# oresat0-1u-backplane.net
KiCad netlist of a schematic drawn in EAGLE
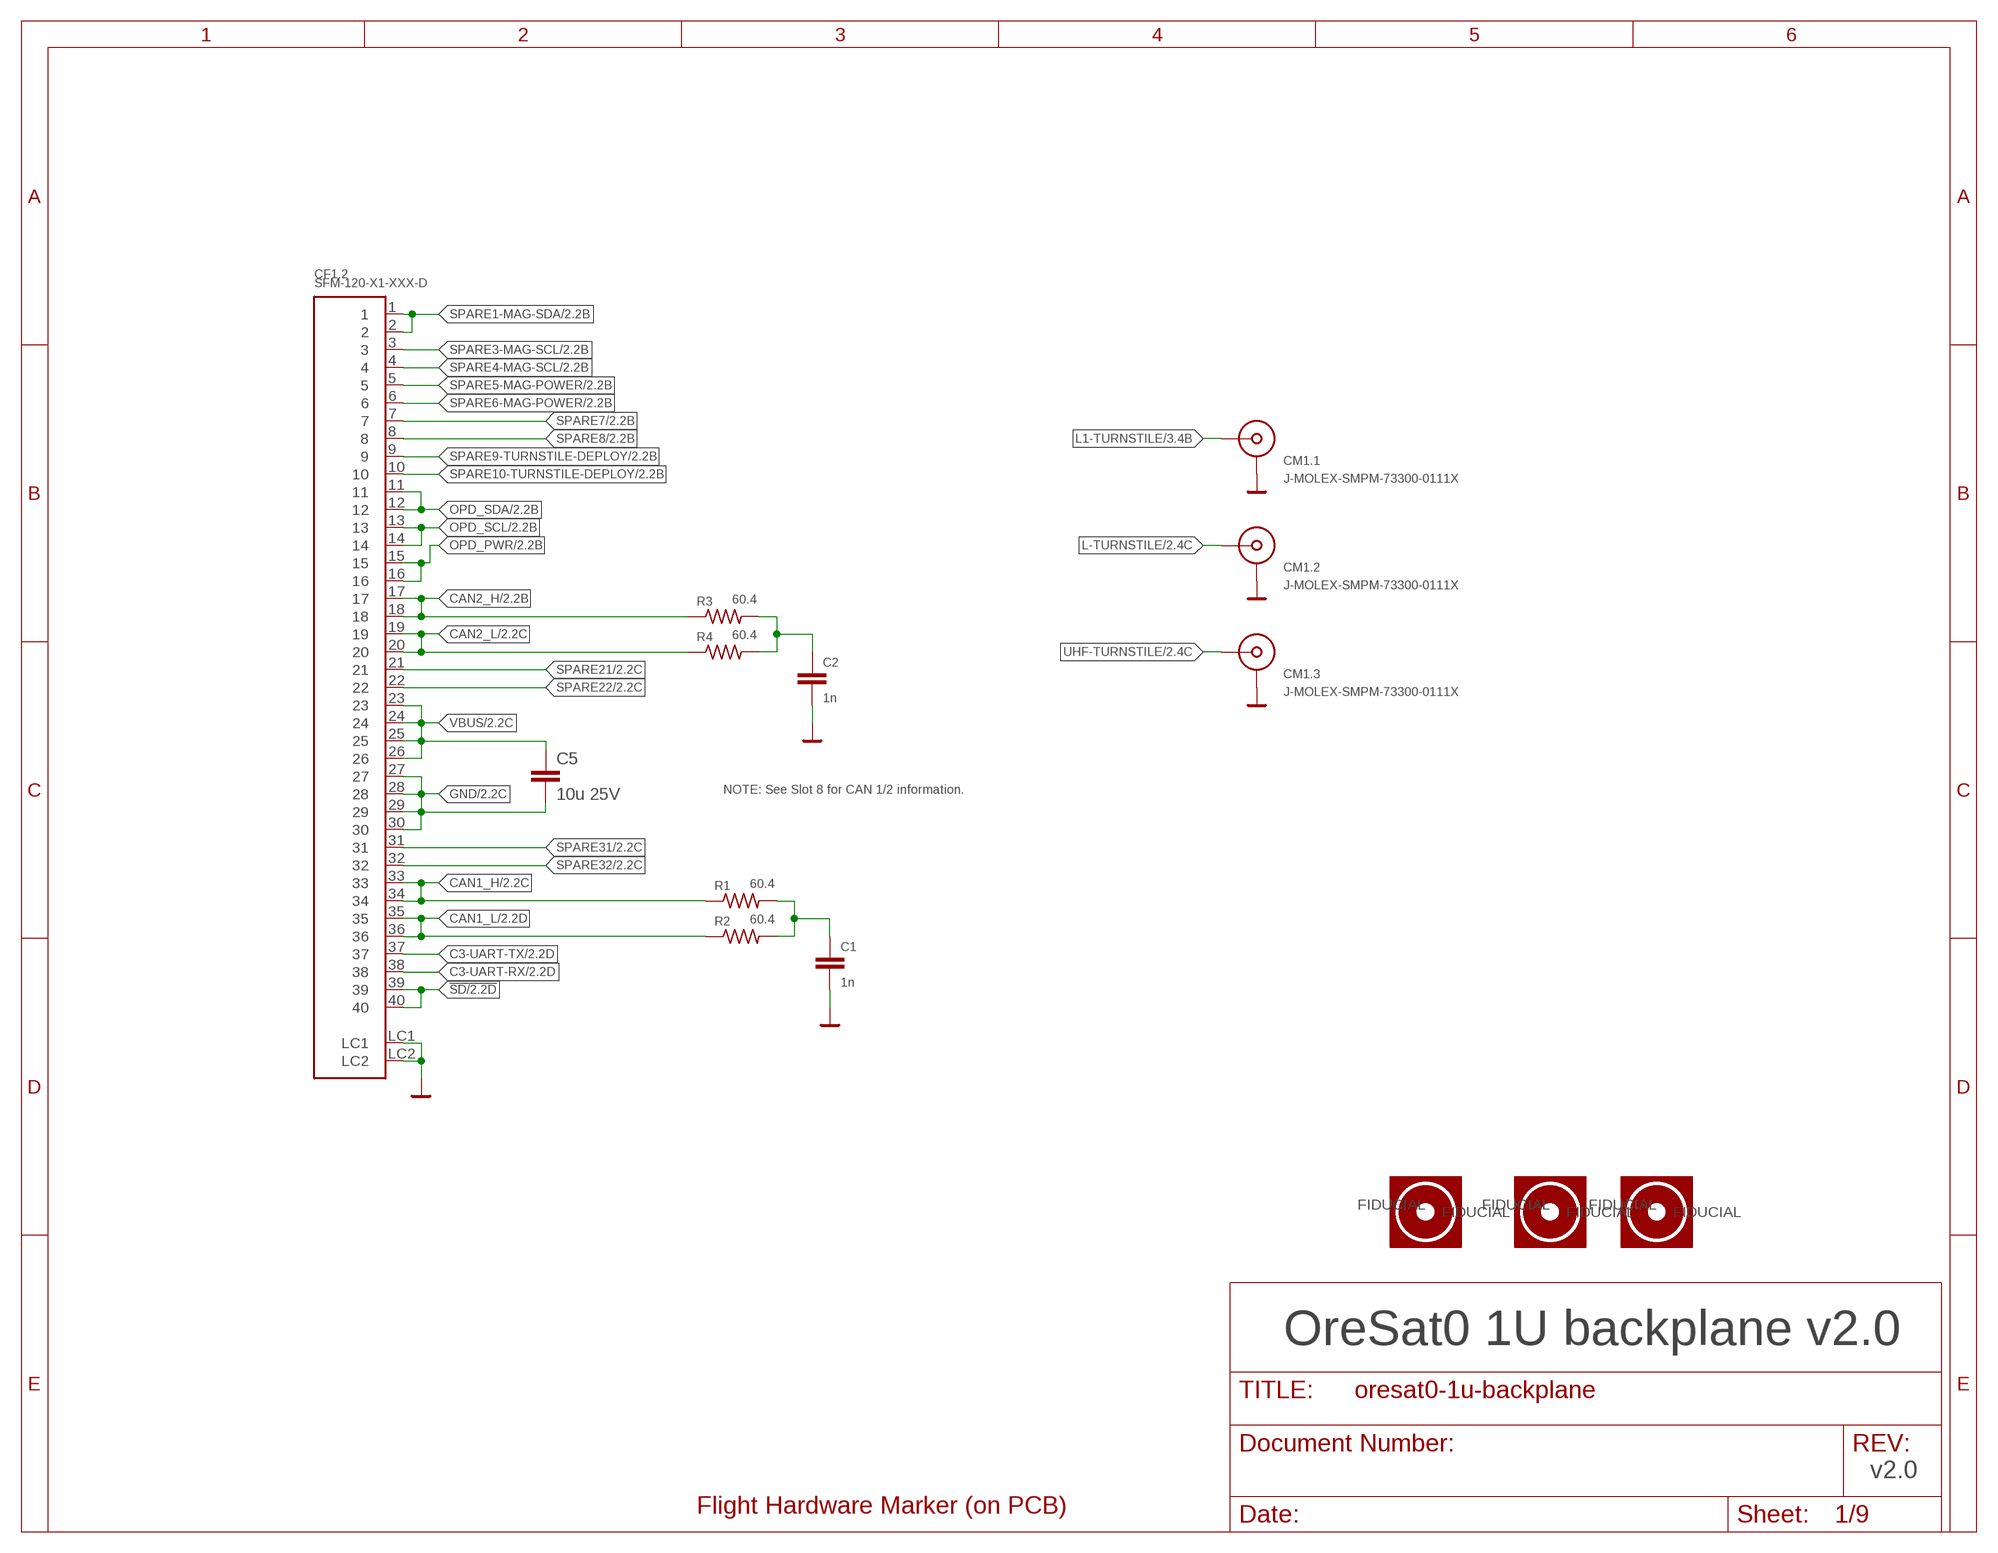
[diagram p0: schematic, sheet 1]
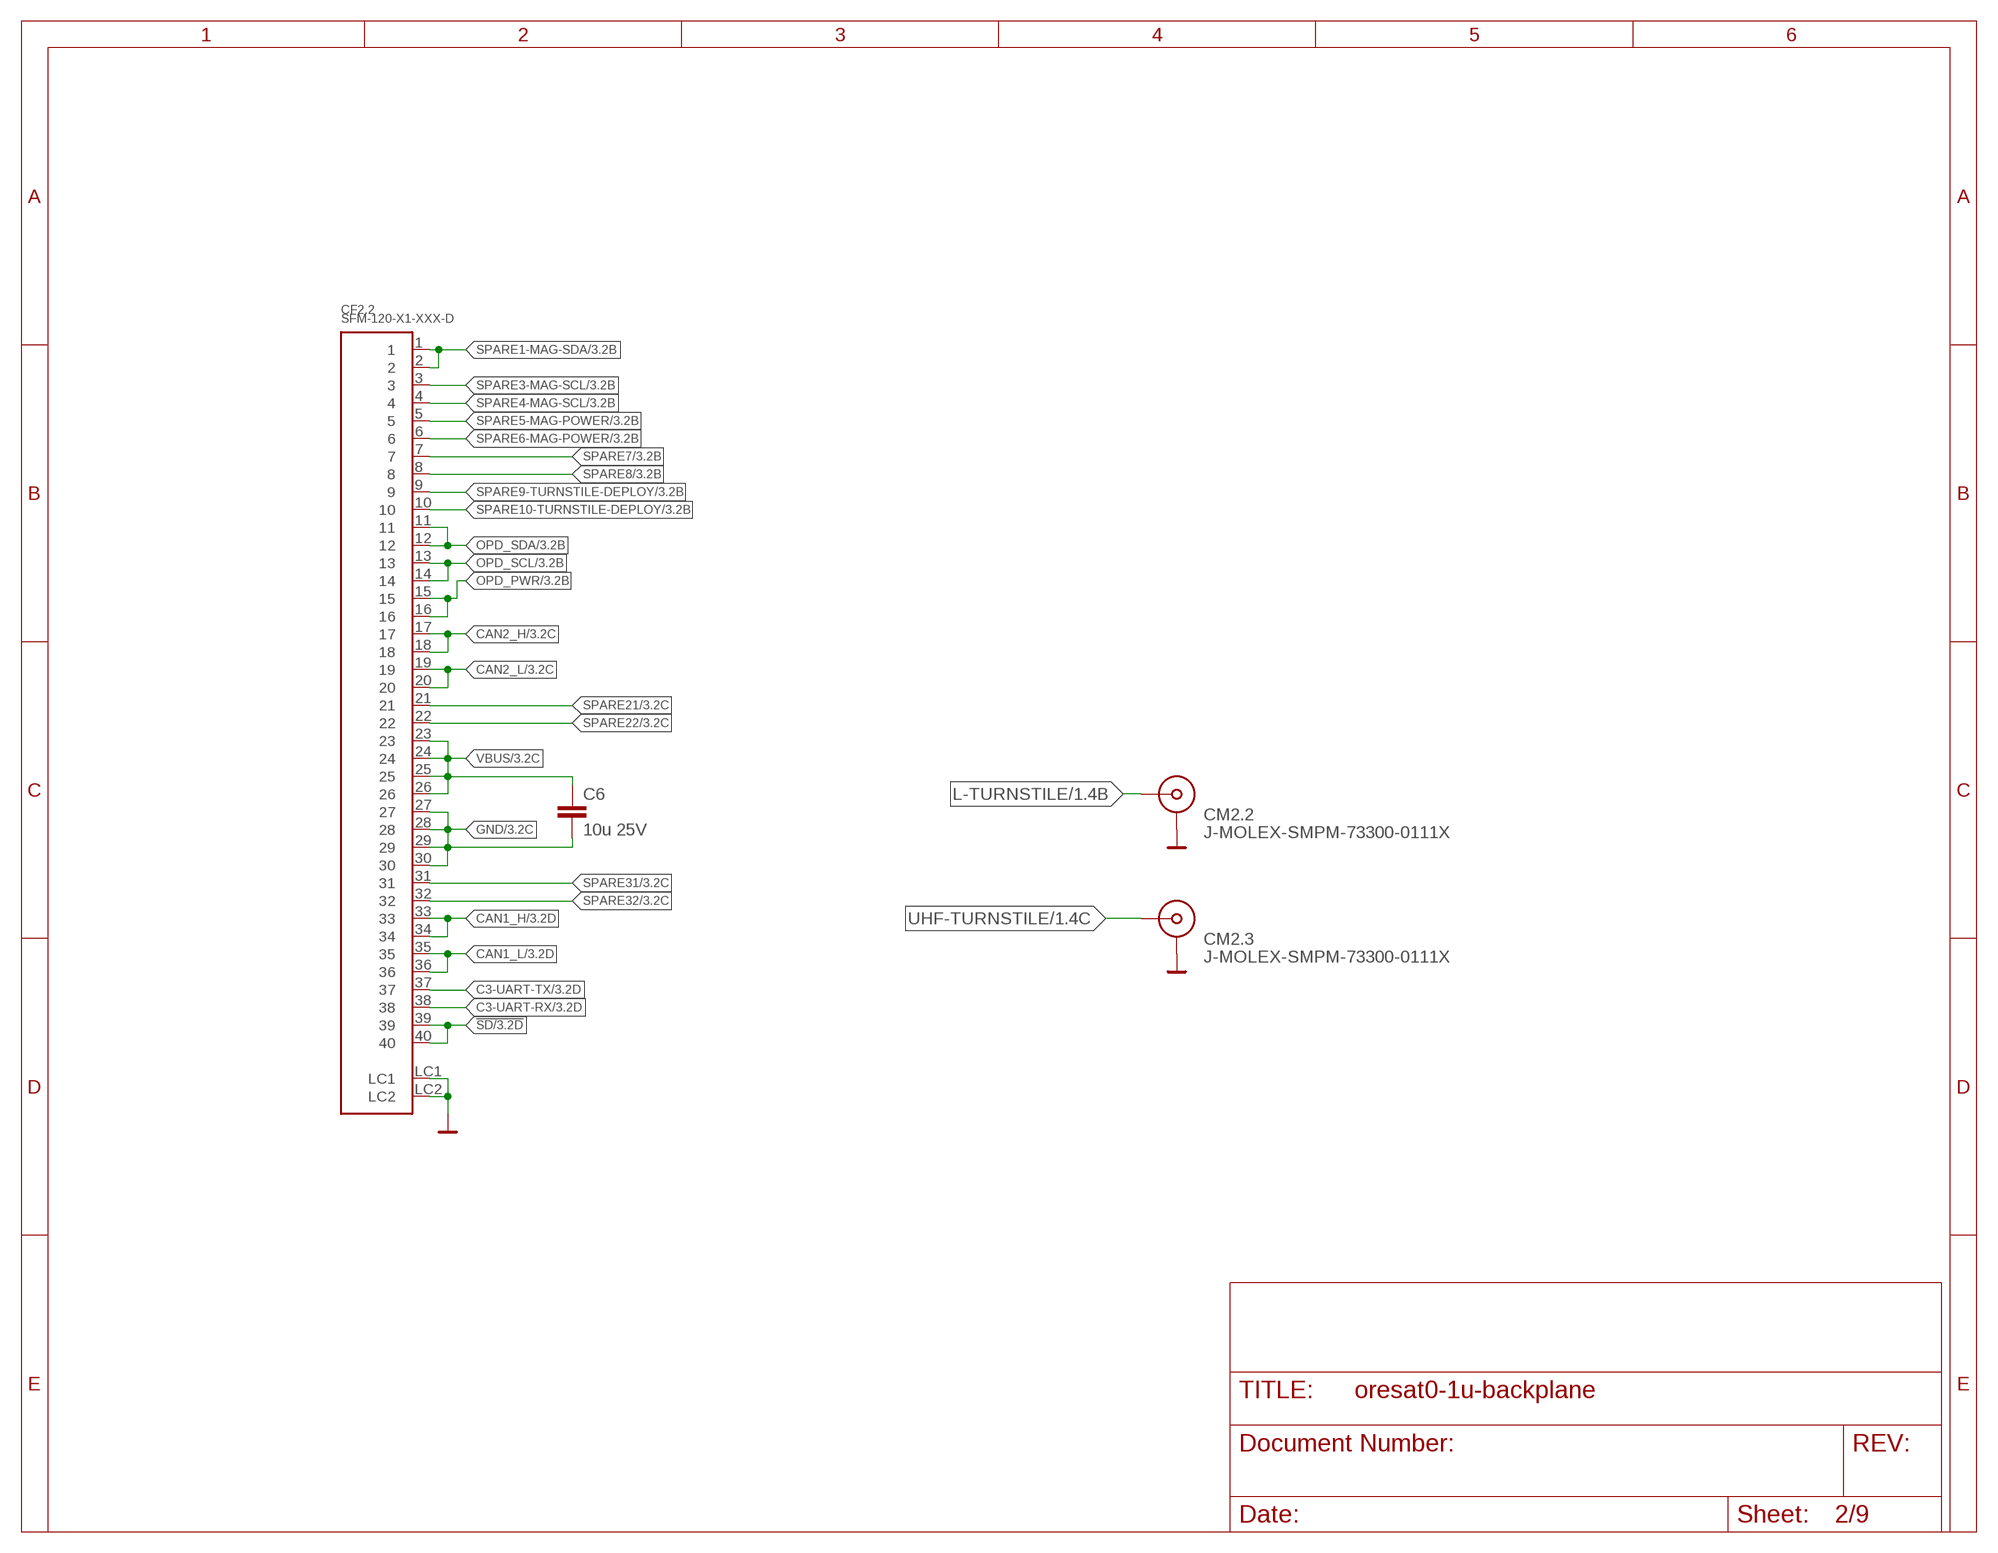
[diagram p1: schematic, sheet 2]
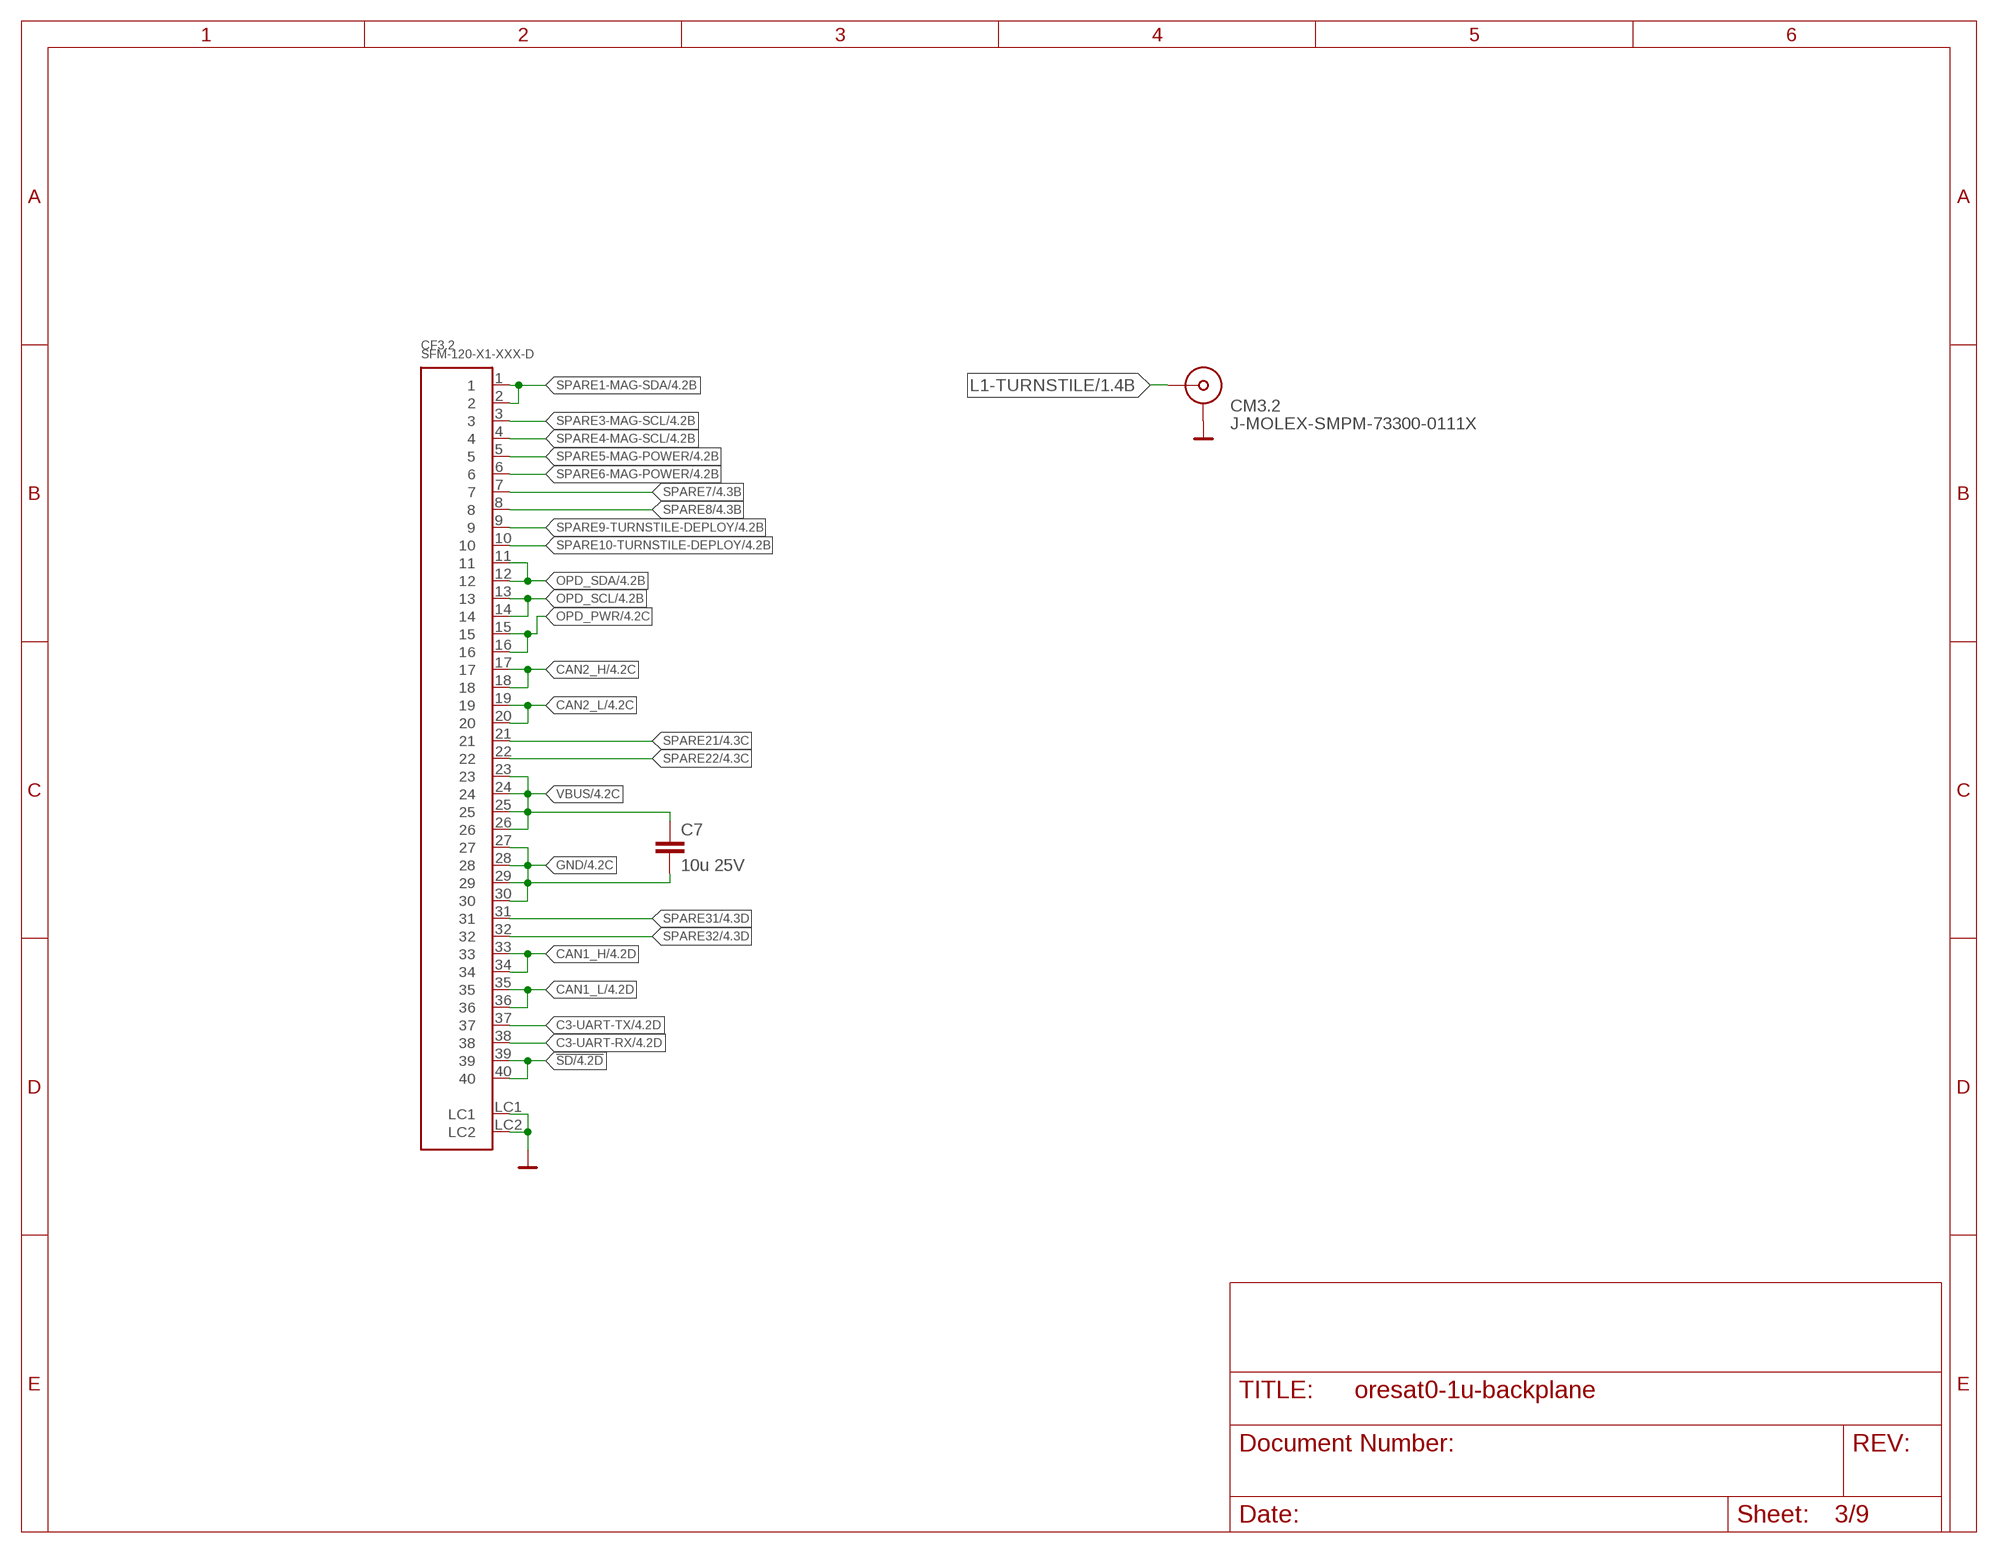
[diagram p2: schematic, sheet 3]
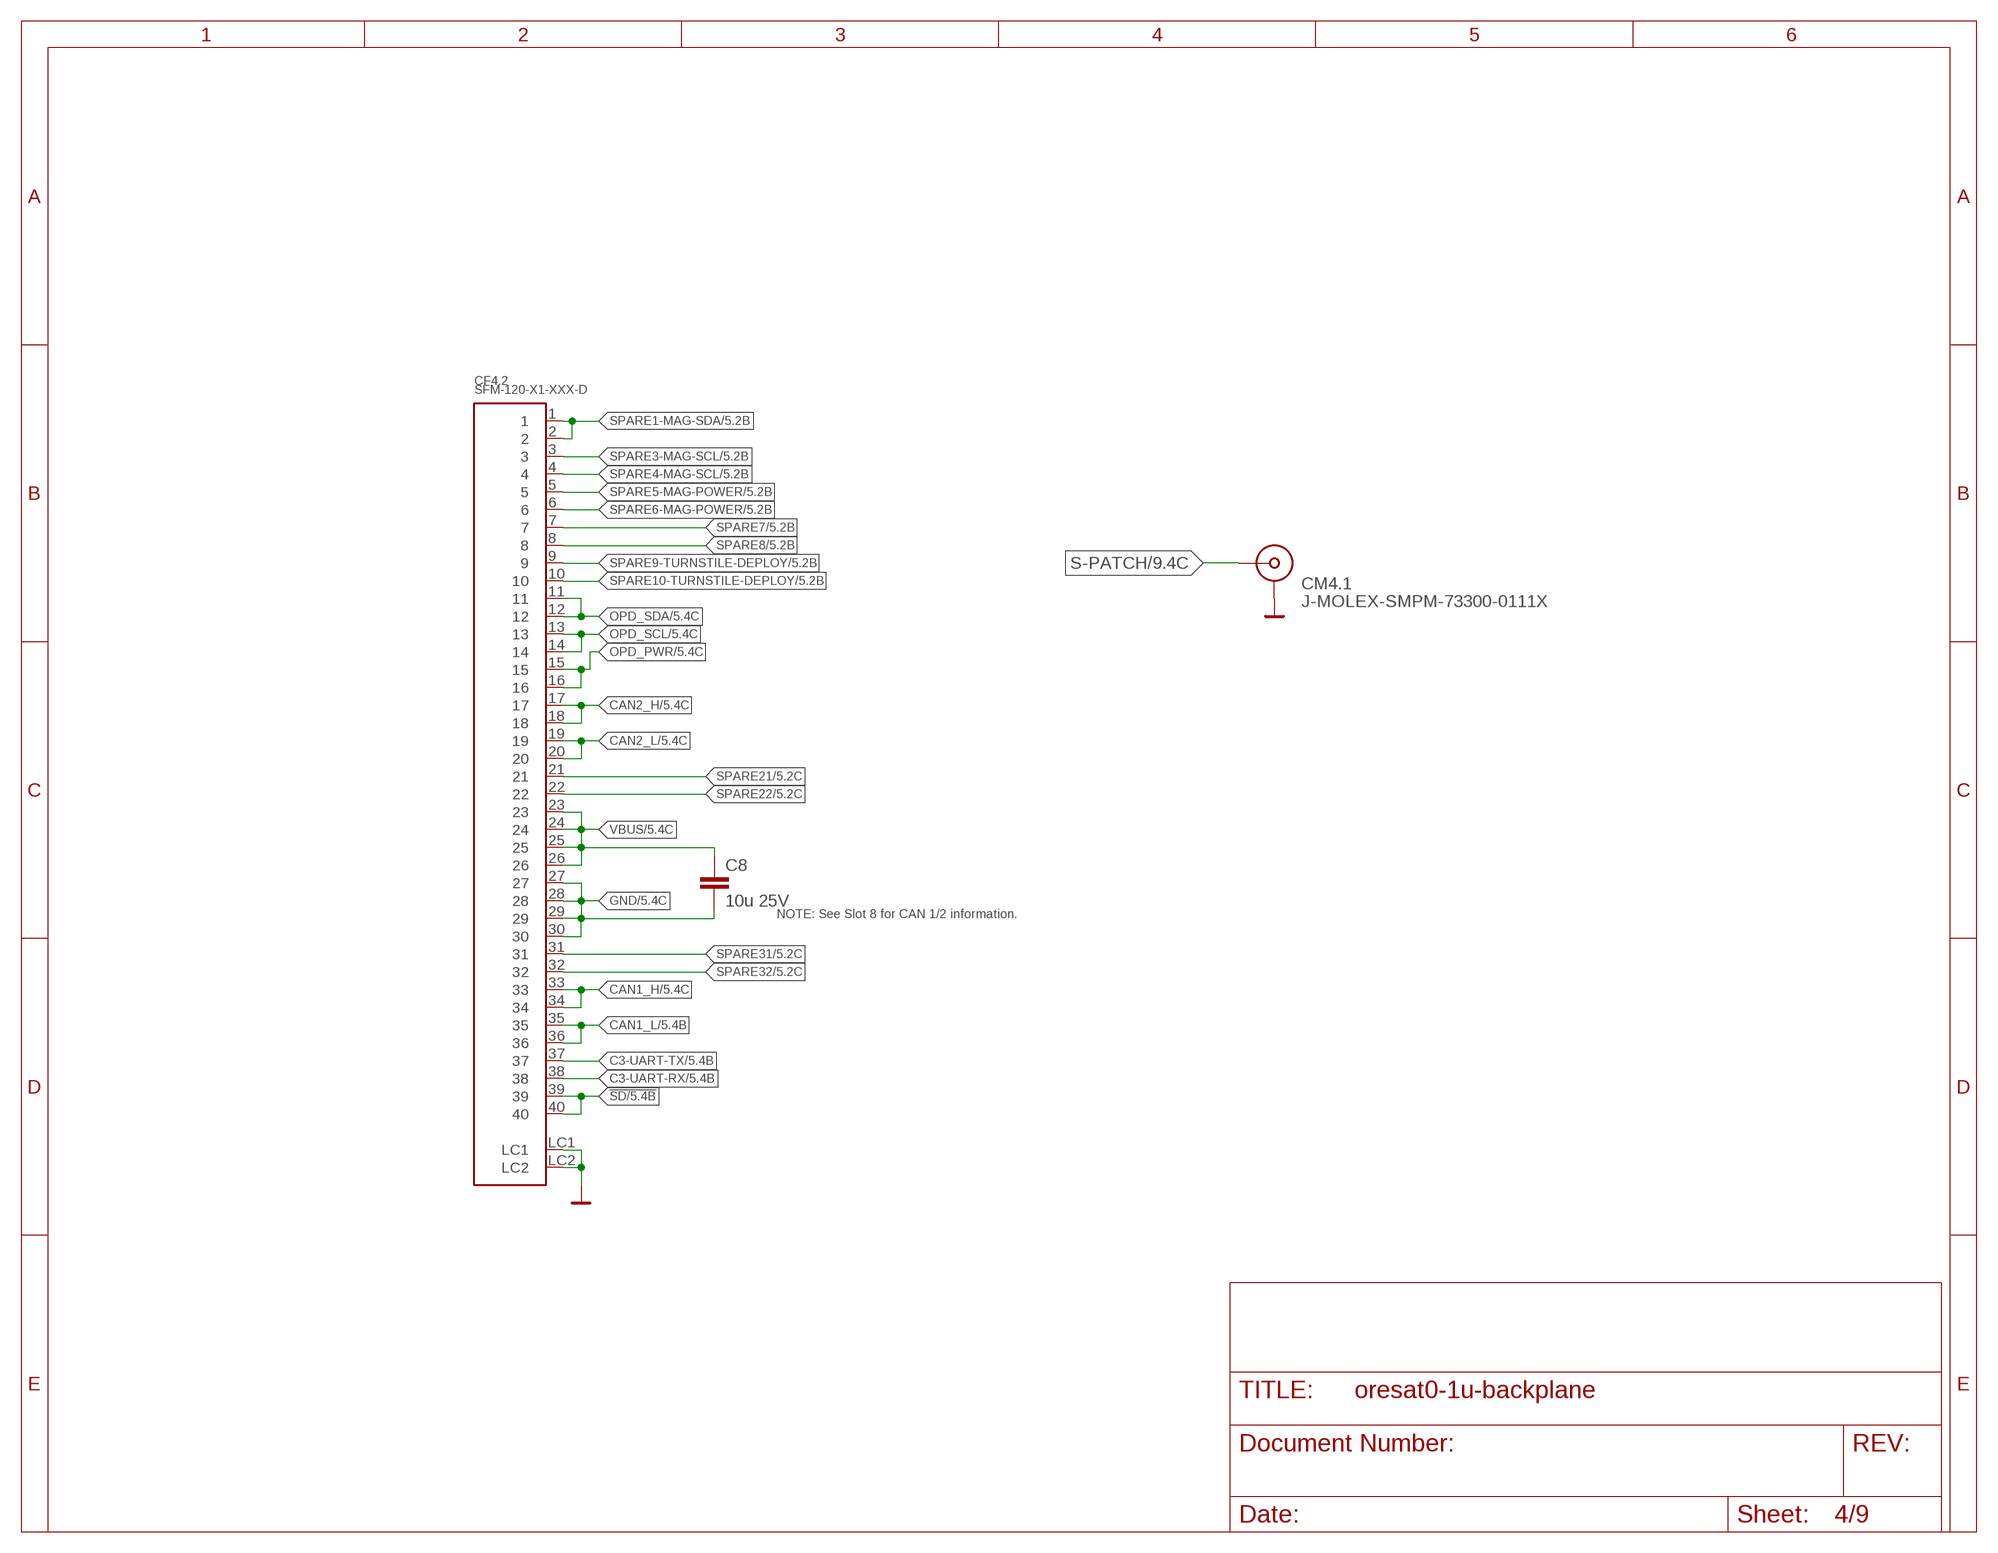
[diagram p3: schematic, sheet 4]
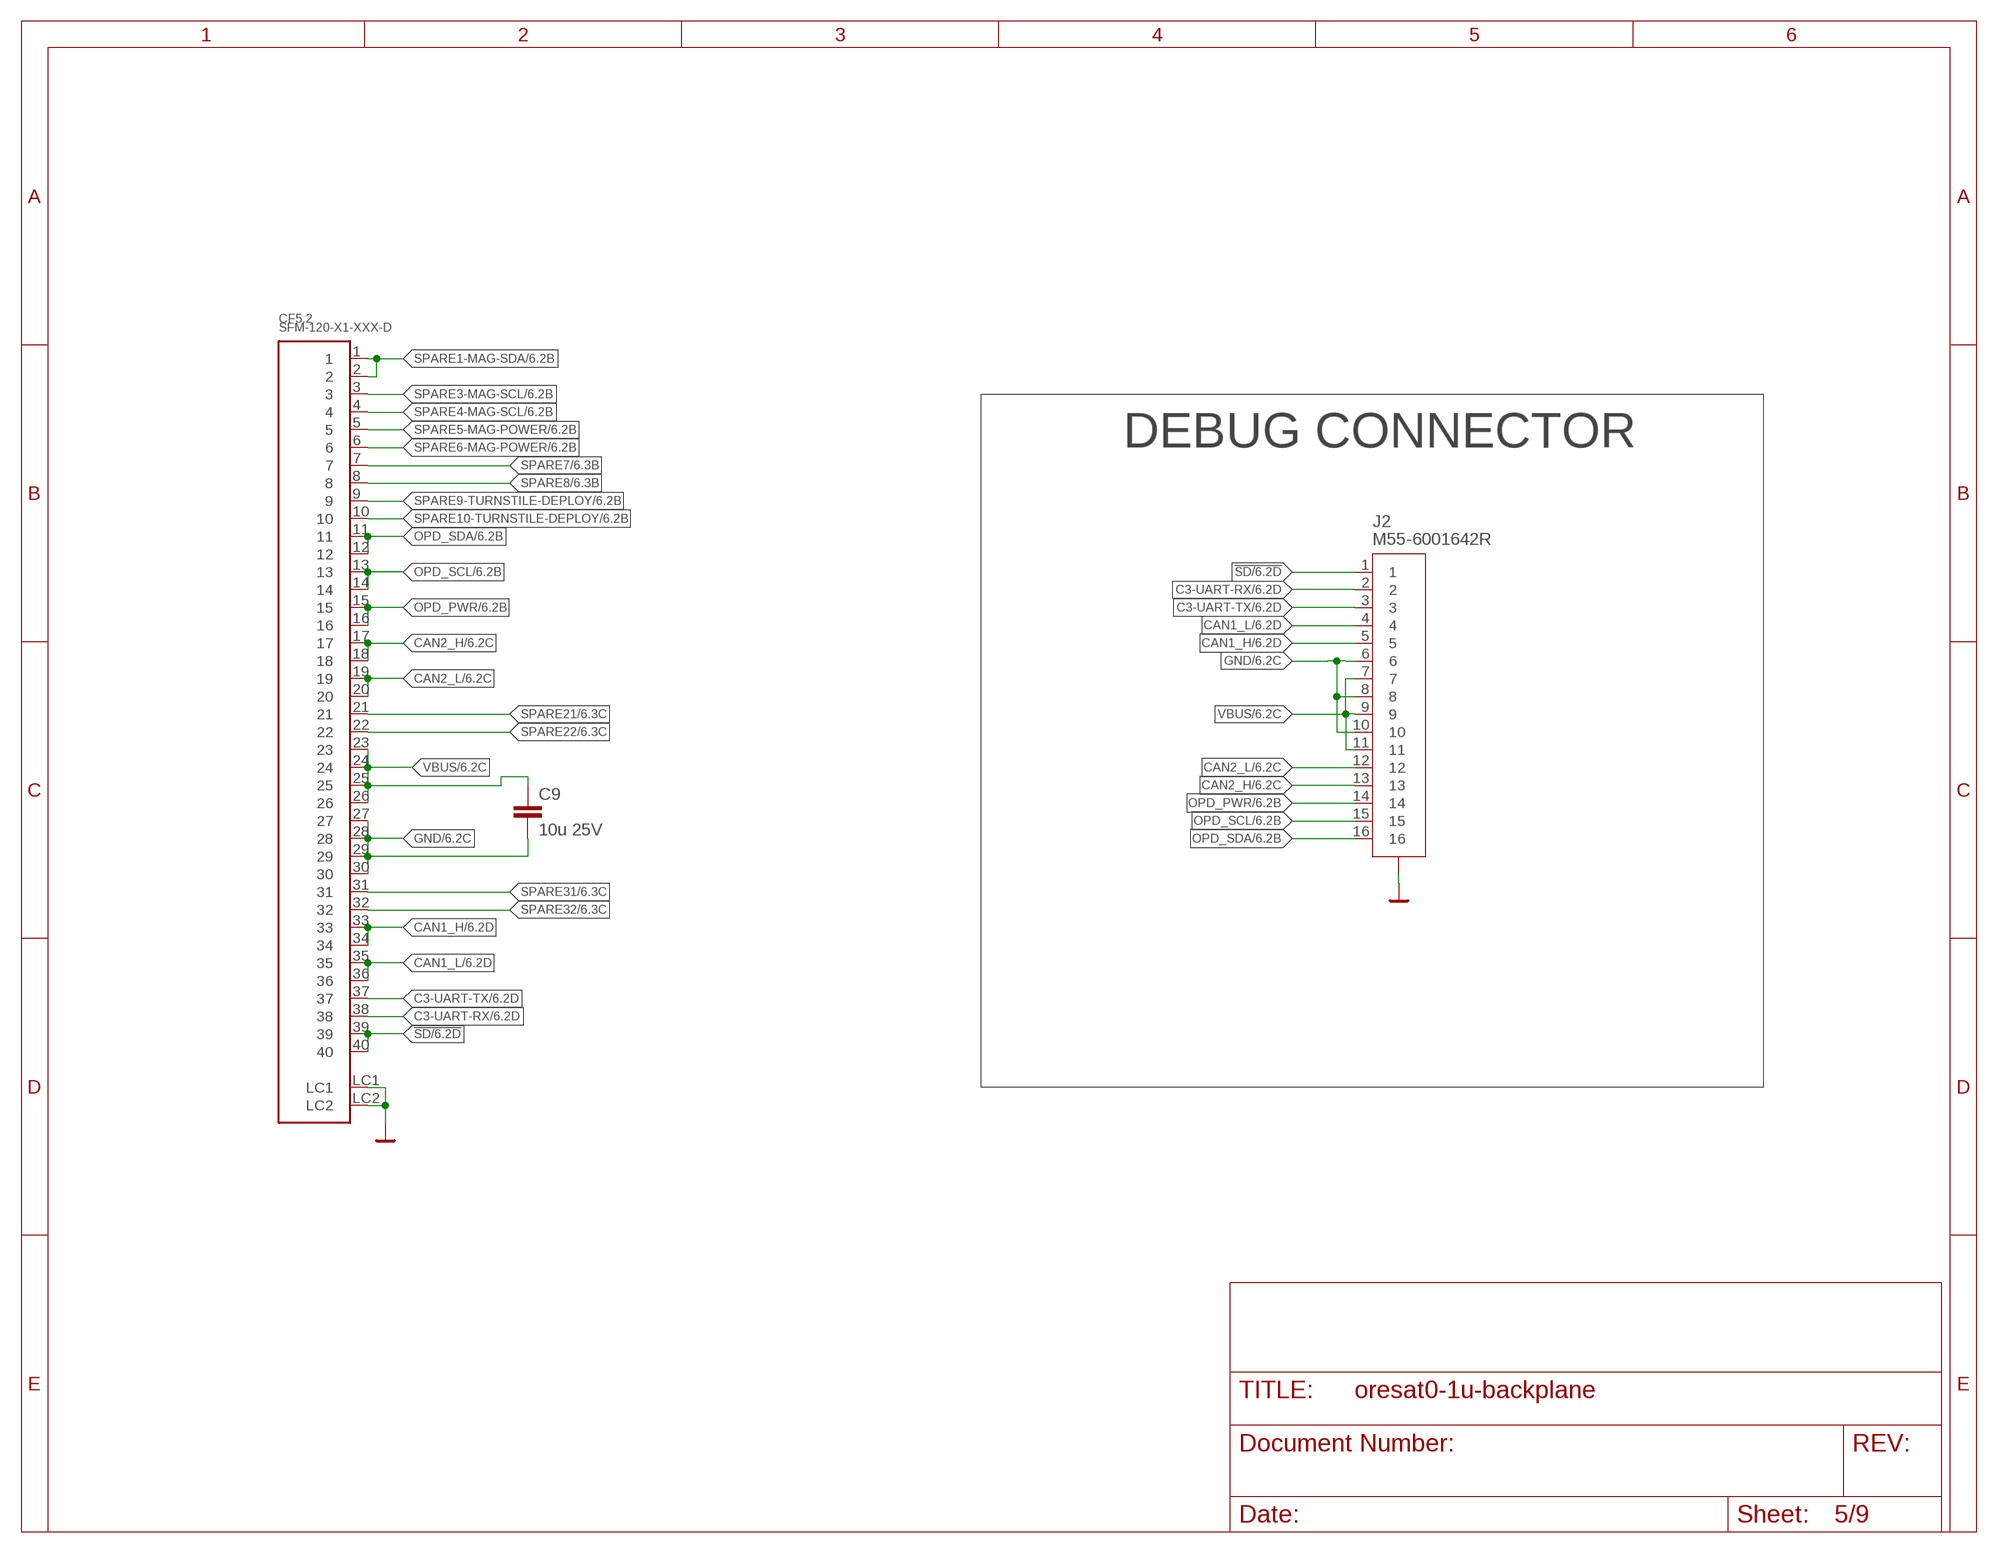
[diagram p4: schematic, sheet 5]
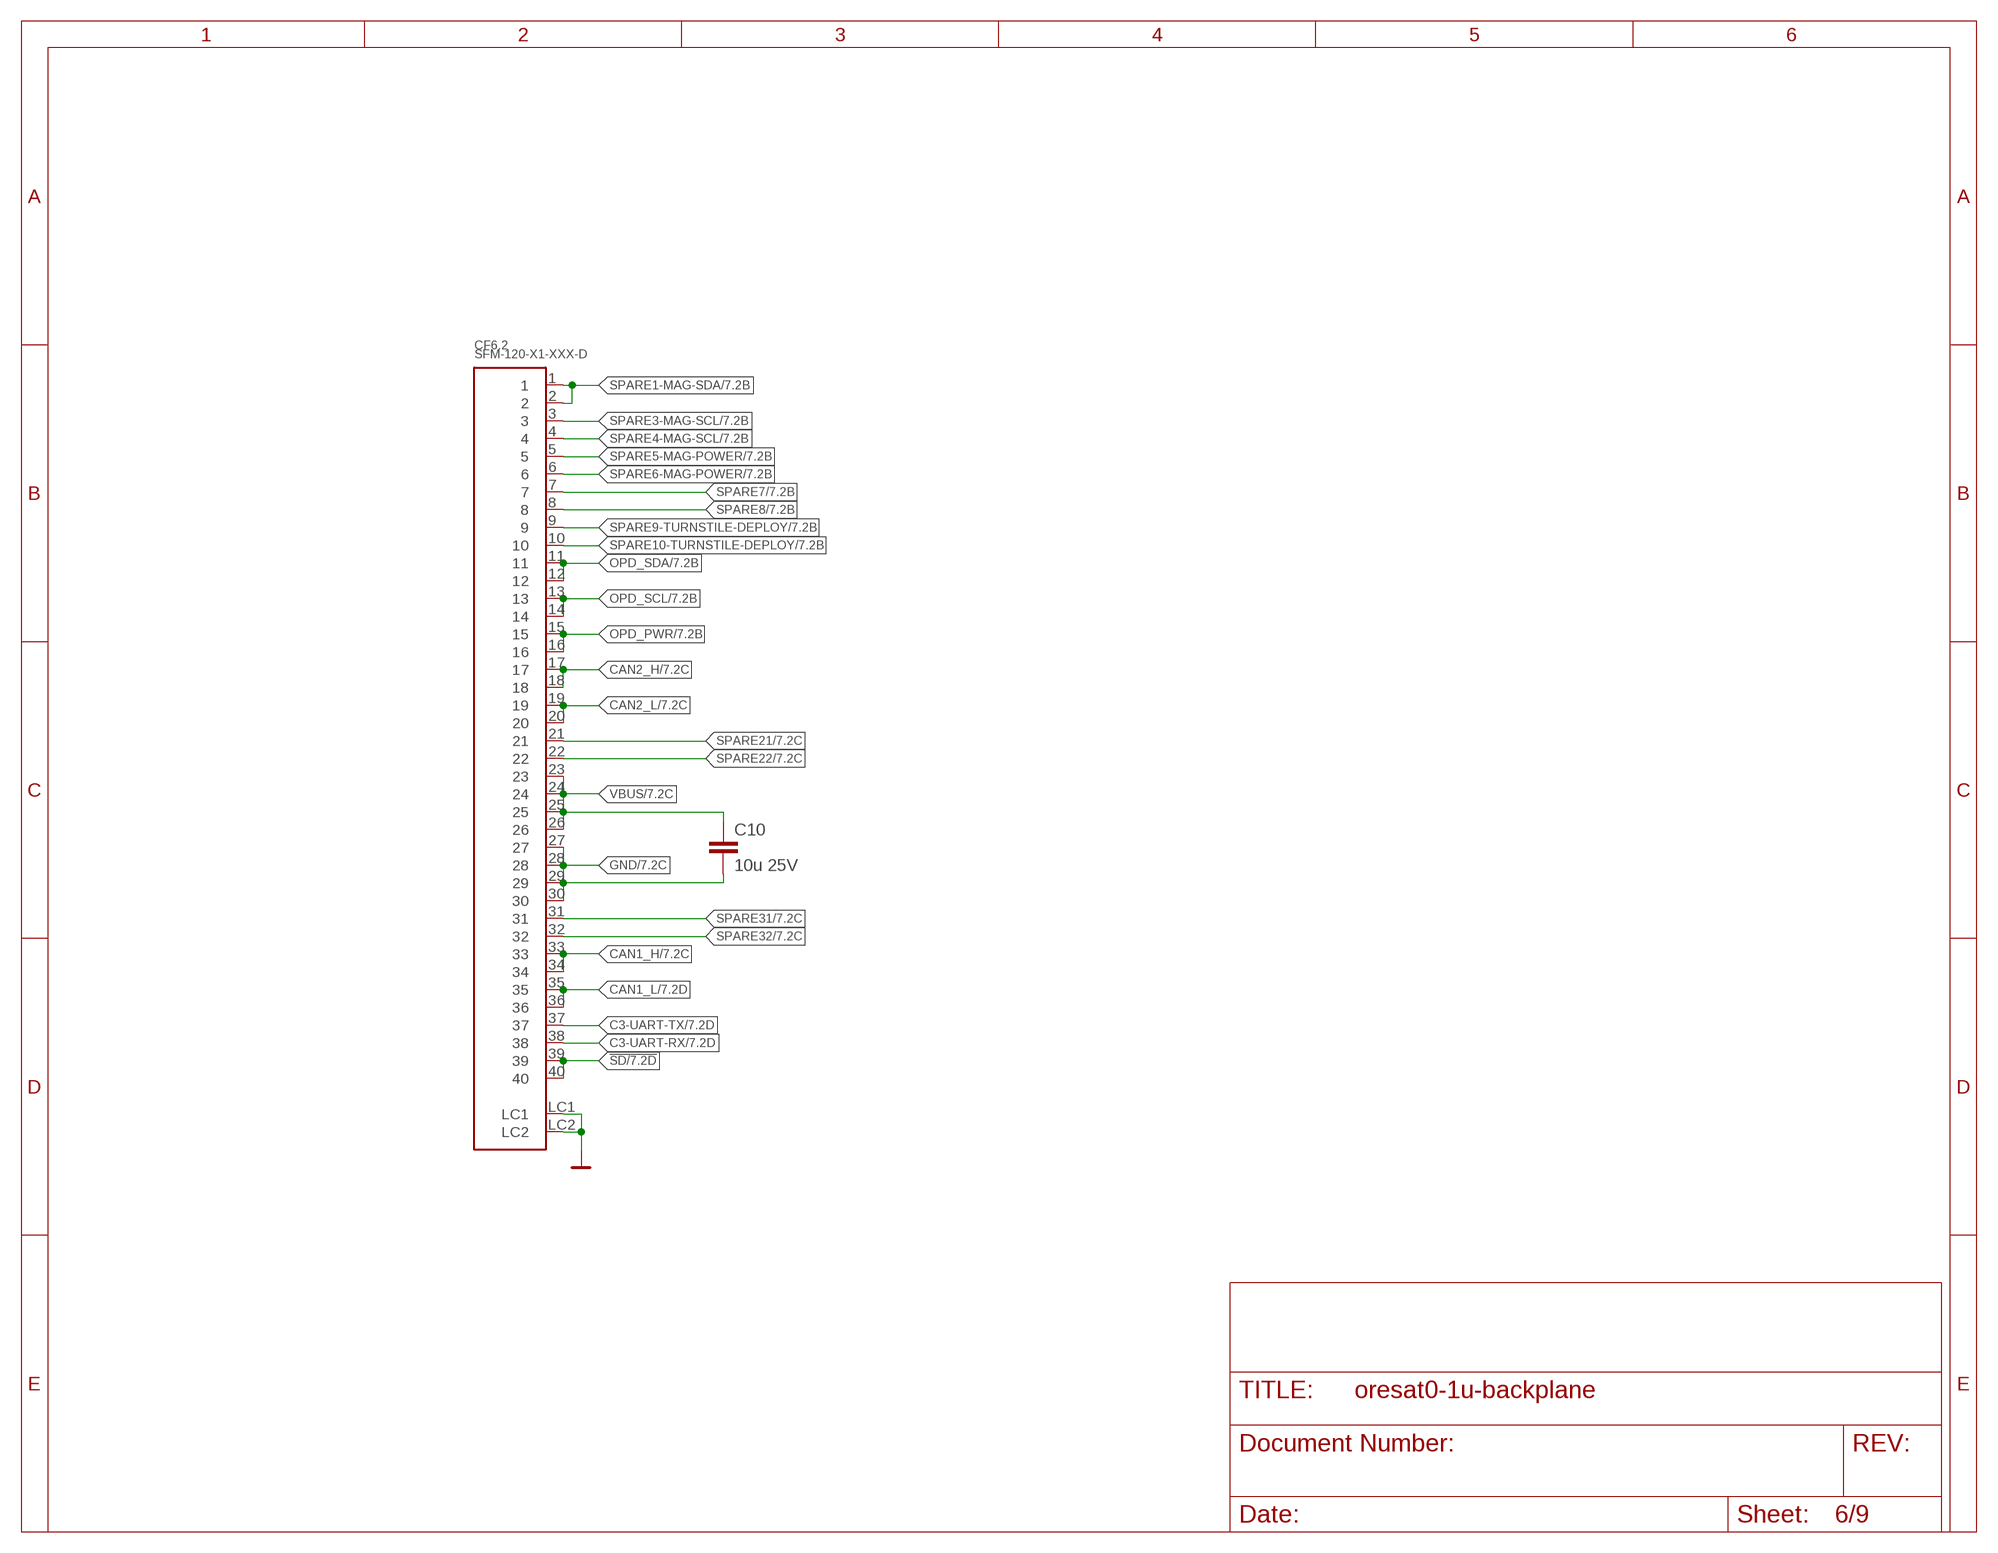
[diagram p5: schematic, sheet 6]
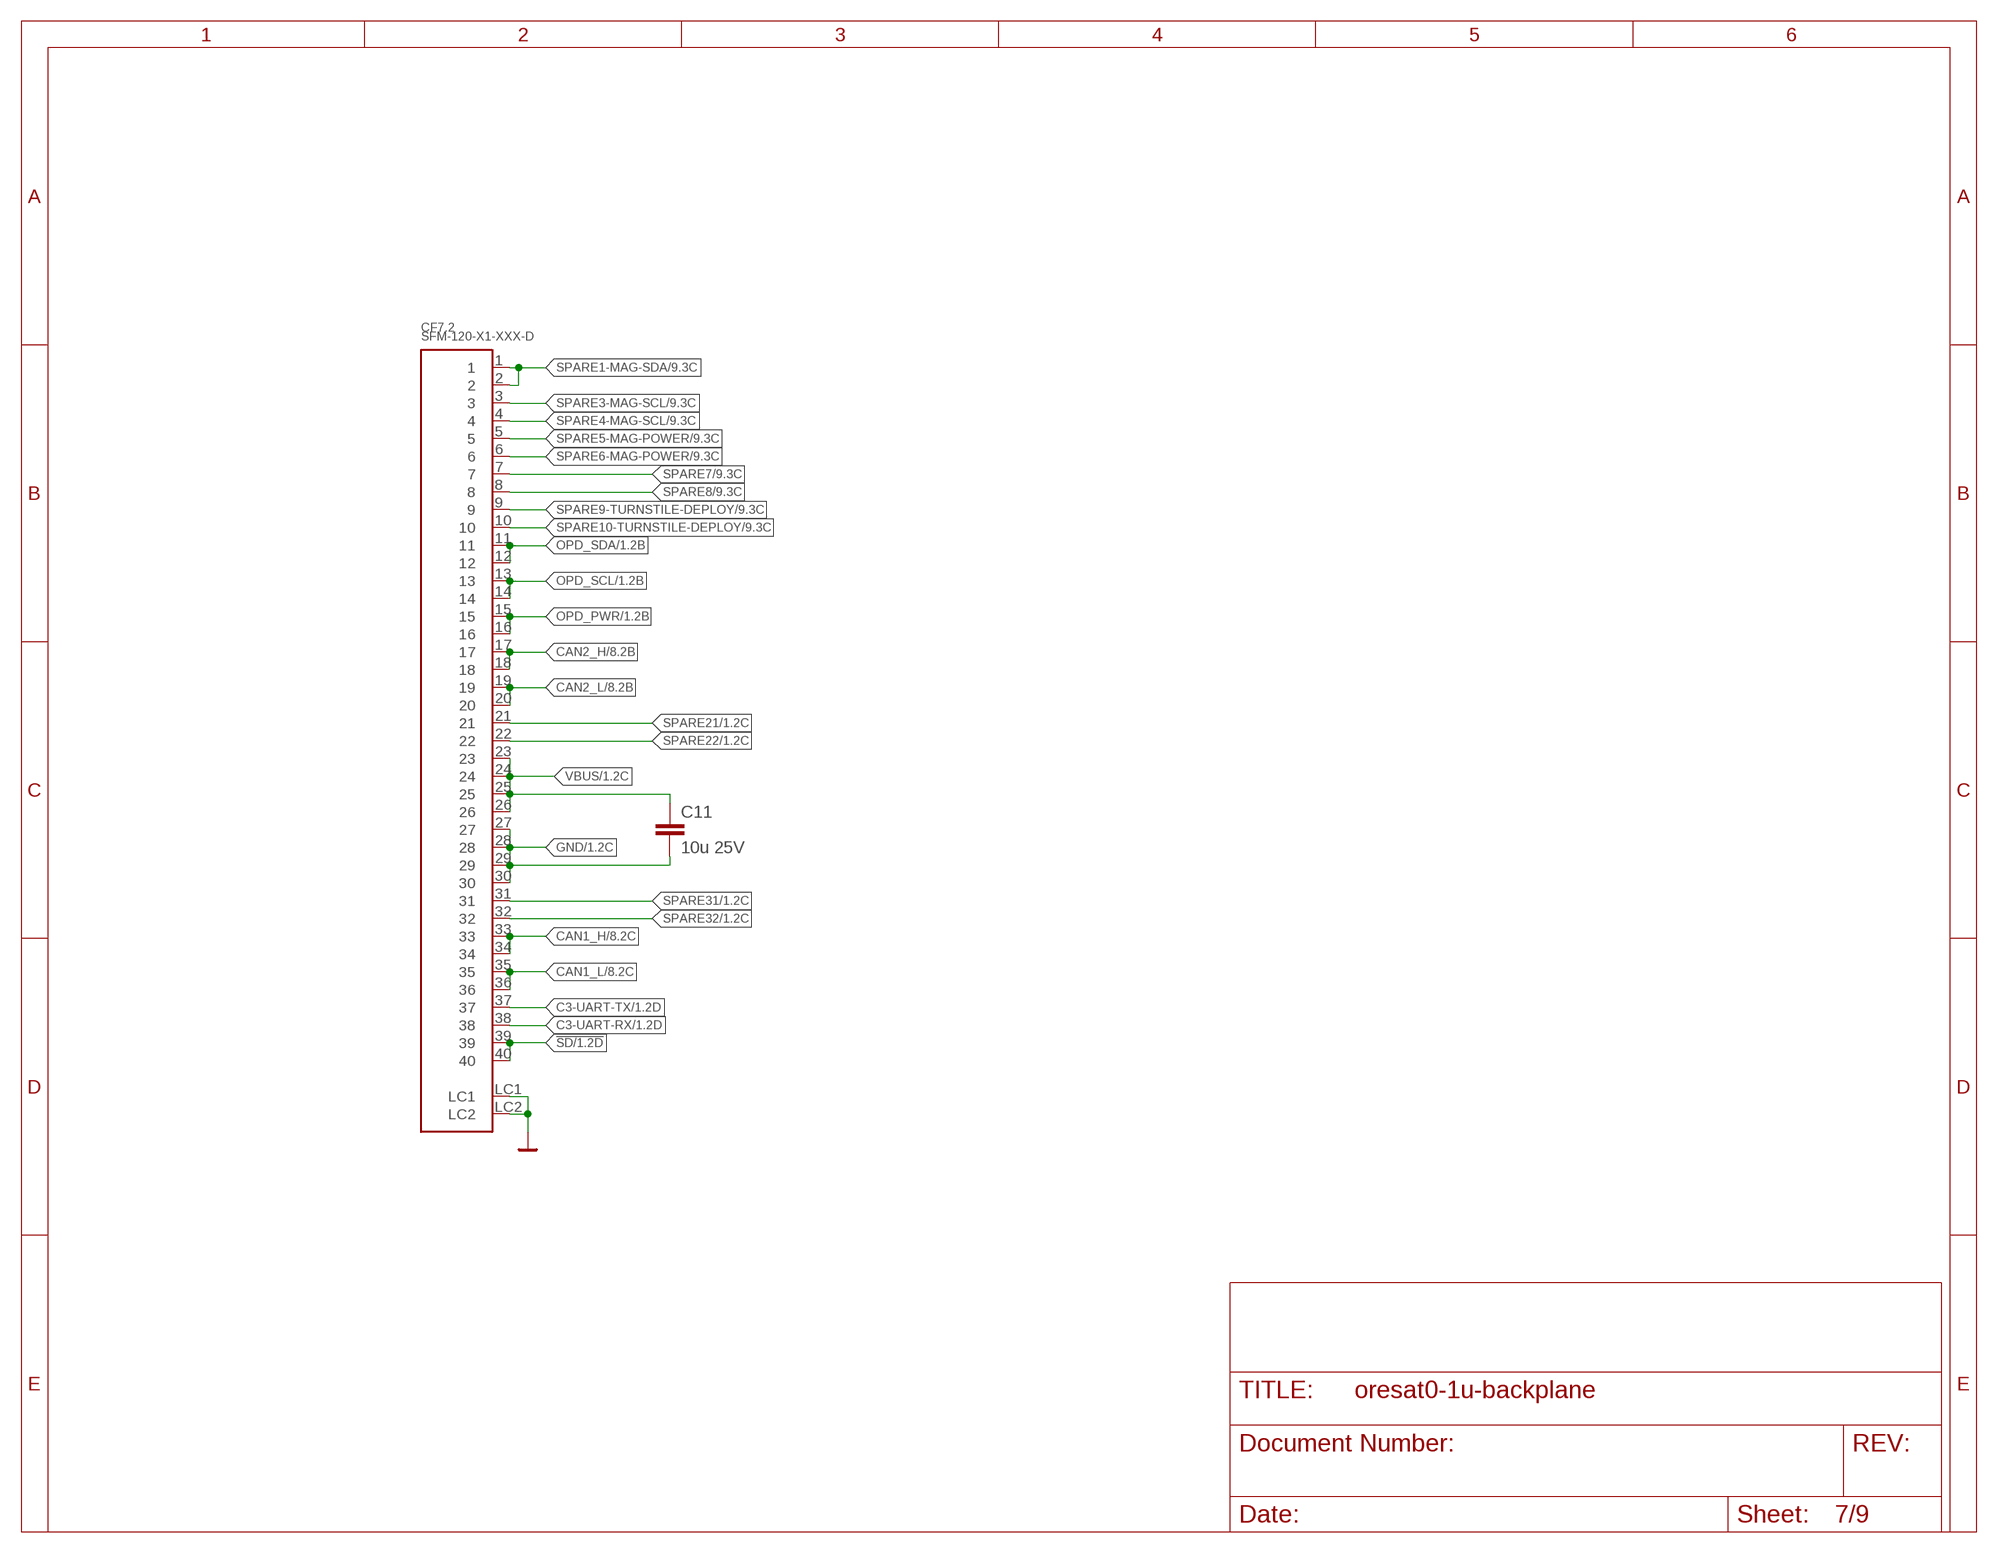
[diagram p6: schematic, sheet 7]
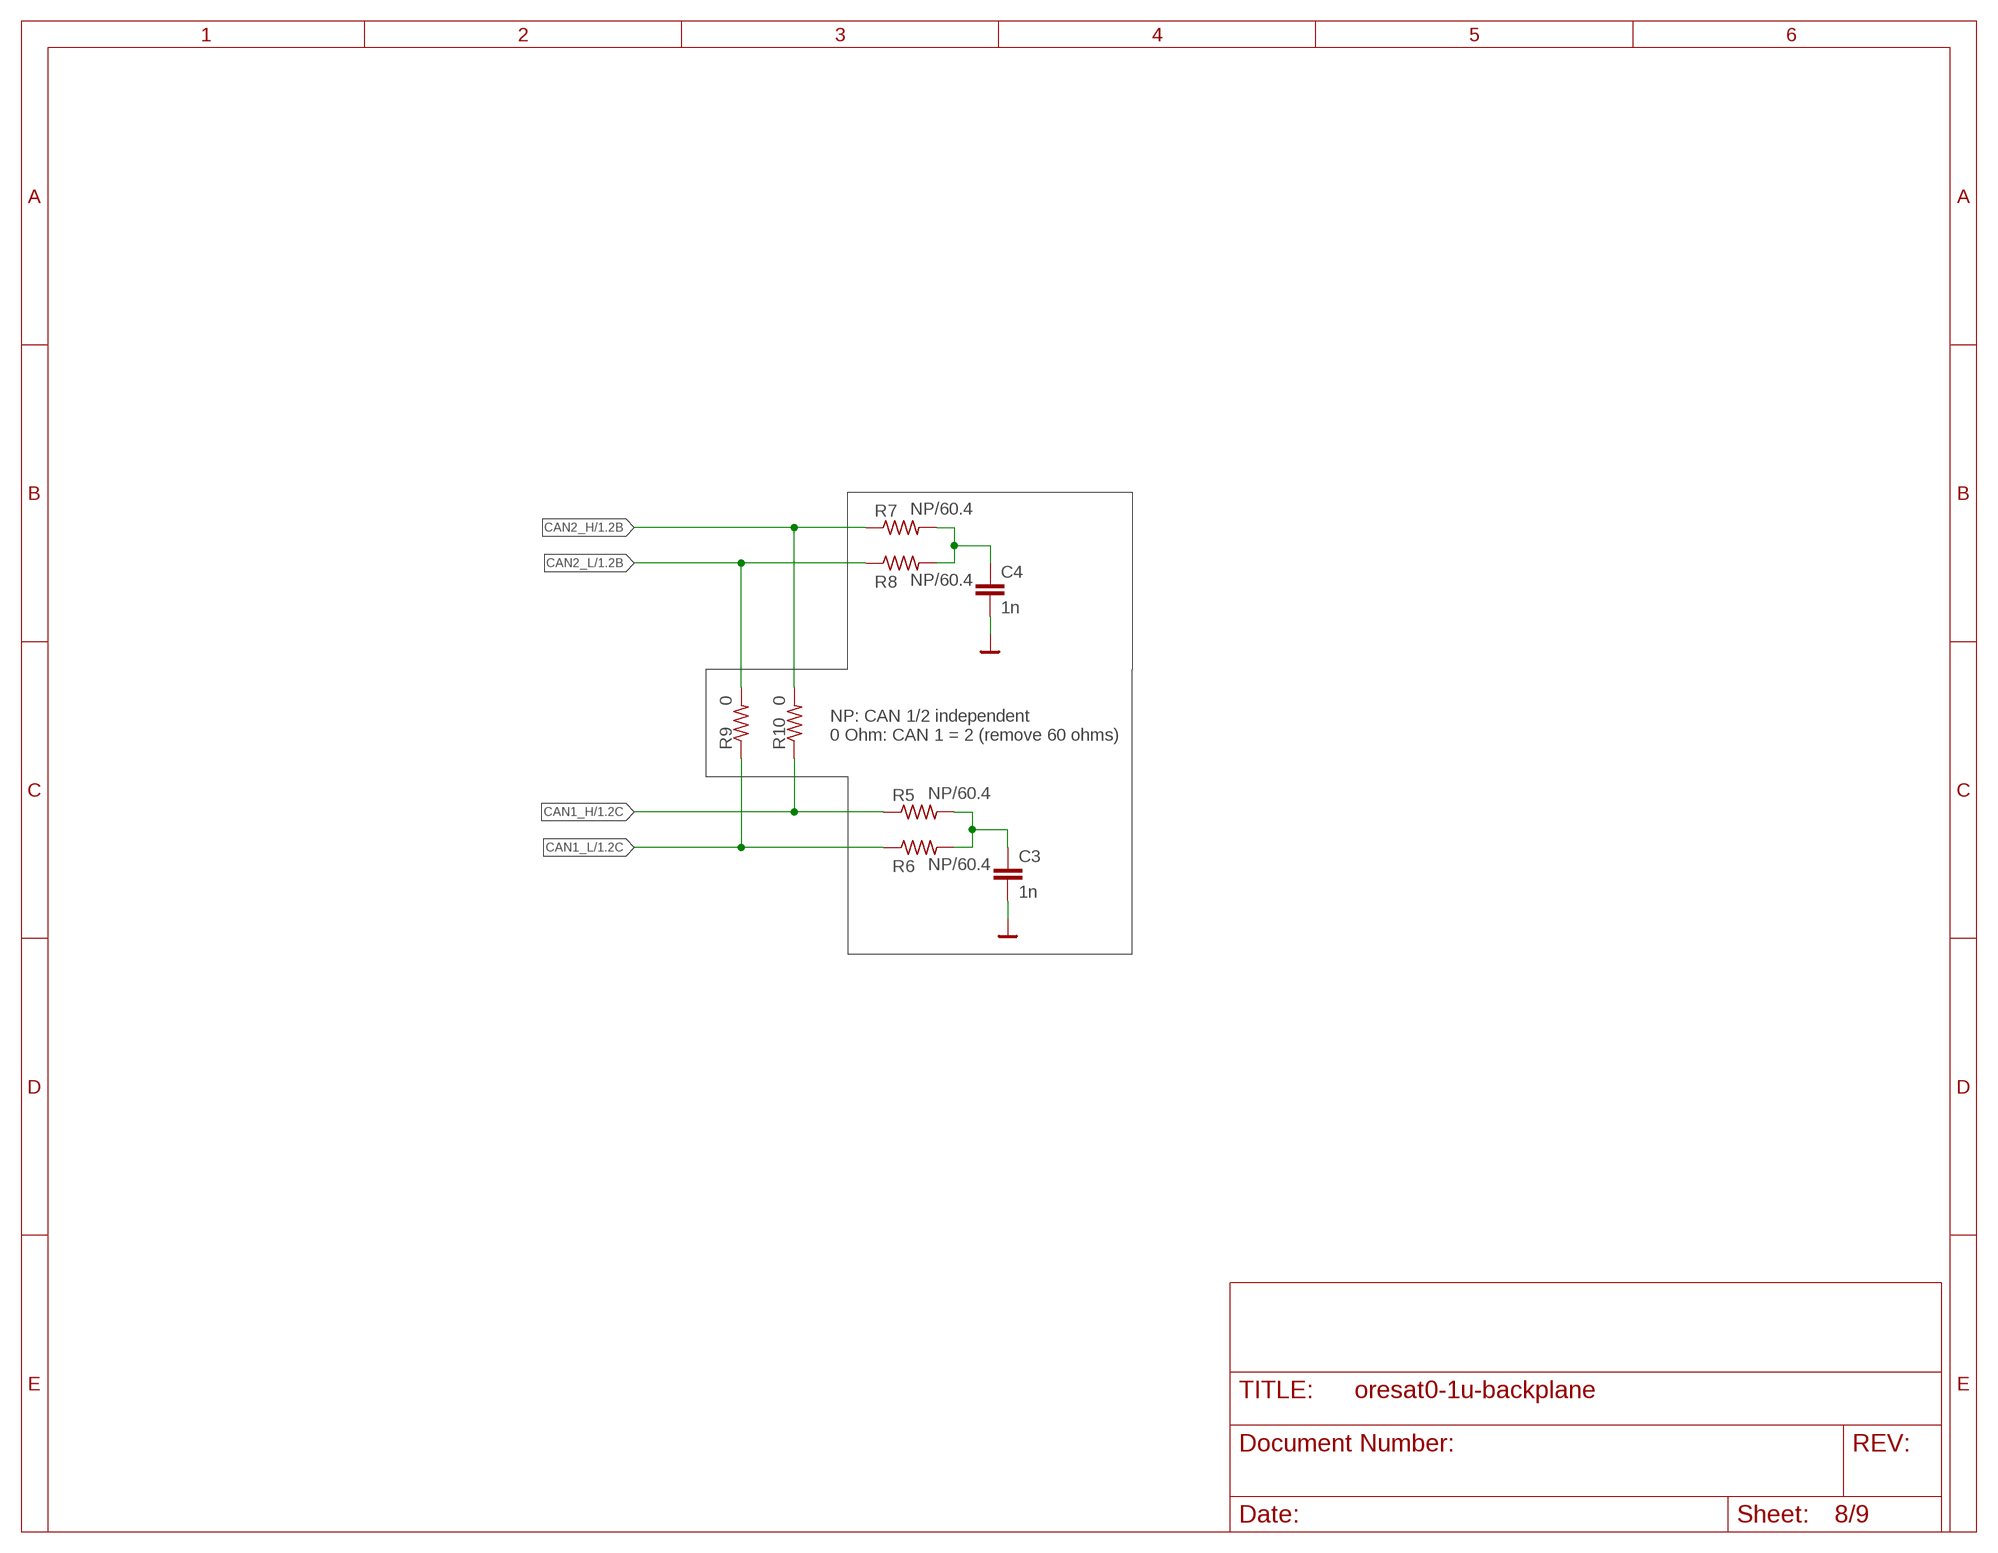
[diagram p7: schematic, sheet 8]
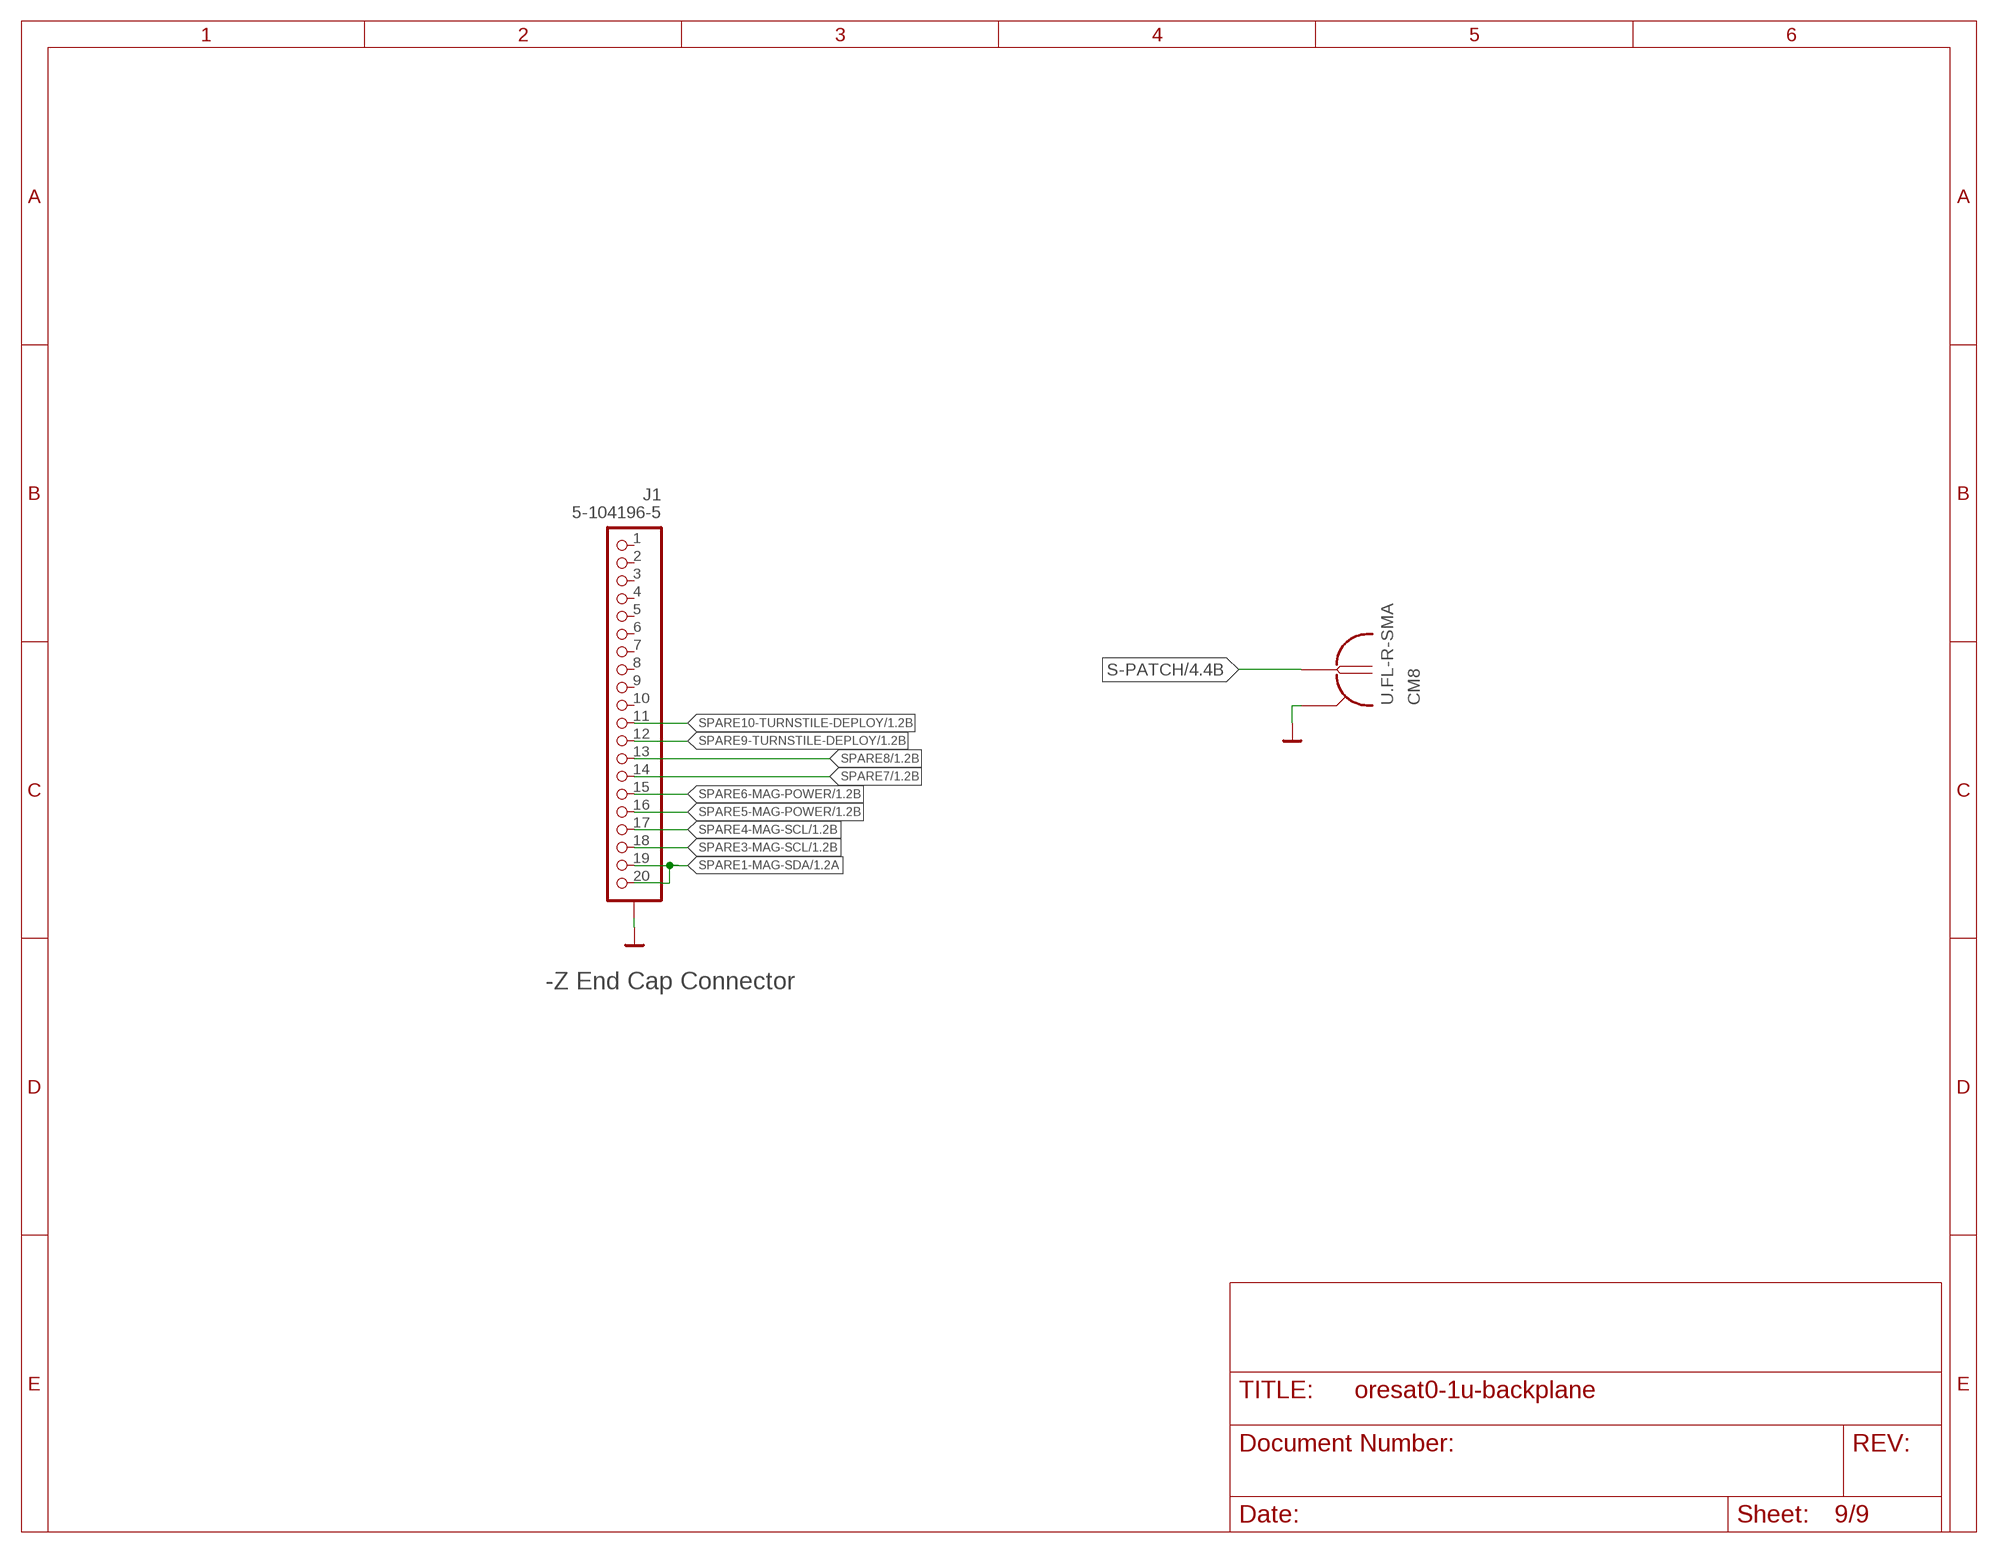
[diagram p8: schematic, sheet 9]

(export (version "E")
  (design (tool "Eeschema 10.0.6"))
  (components
    (comp (ref "C11")
      (value "10u 25V")
      (footprint "eagle-import:1206-B")
      (libsource (lib "eagle-import") (part "C-EU1206-B"))
    )
    (comp (ref "CF7.2")
      (value "SFM-120-X1-XXX-D")
      (footprint "eagle-import:SFM-120-X1-XXX-D")
      (libsource (lib "eagle-import") (part "SFM-120-X1-XXX-D"))
    )
    (comp (ref "C3")
      (value "1n")
      (footprint "eagle-import:.0603-C-NOSILK")
      (libsource (lib "eagle-import") (part "C-EU0603-C-NOSILK"))
    )
    (comp (ref "C4")
      (value "1n")
      (footprint "eagle-import:.0603-C-NOSILK")
      (libsource (lib "eagle-import") (part "C-EU0603-C-NOSILK"))
    )
    (comp (ref "R5")
      (value "NP/60.4")
      (footprint "eagle-import:1206-C")
      (libsource (lib "eagle-import") (part "R-US_1206-C"))
    )
    (comp (ref "R6")
      (value "NP/60.4")
      (footprint "eagle-import:1206-C")
      (libsource (lib "eagle-import") (part "R-US_1206-C"))
    )
    (comp (ref "R7")
      (value "NP/60.4")
      (footprint "eagle-import:1206-C")
      (libsource (lib "eagle-import") (part "R-US_1206-C"))
    )
    (comp (ref "R8")
      (value "NP/60.4")
      (footprint "eagle-import:1206-C")
      (libsource (lib "eagle-import") (part "R-US_1206-C"))
    )
    (comp (ref "R9")
      (value "0")
      (footprint "eagle-import:.0603-B-NOSILK")
      (libsource (lib "eagle-import") (part "R-US_0603-B-NOSILK"))
    )
    (comp (ref "R10")
      (value "0")
      (footprint "eagle-import:.0603-B-NOSILK")
      (libsource (lib "eagle-import") (part "R-US_0603-B-NOSILK"))
    )
    (comp (ref "C6")
      (value "10u 25V")
      (footprint "eagle-import:1206-B")
      (libsource (lib "eagle-import") (part "C-EU1206-B"))
    )
    (comp (ref "CF2.2")
      (value "SFM-120-X1-XXX-D")
      (footprint "eagle-import:SFM-120-X1-XXX-D")
      (libsource (lib "eagle-import") (part "SFM-120-X1-XXX-D"))
    )
    (comp (ref "CM2.2")
      (value "J-MOLEX-SMPM-73300-0111X")
      (footprint "eagle-import:J-MOLEX-SMPM-73300-0111X")
      (libsource (lib "eagle-import") (part "J-MOLEX-SMPM-73300-0111X"))
    )
    (comp (ref "CM2.3")
      (value "J-MOLEX-SMPM-73300-0111X")
      (footprint "eagle-import:J-MOLEX-SMPM-73300-0111X")
      (libsource (lib "eagle-import") (part "J-MOLEX-SMPM-73300-0111X"))
    )
    (comp (ref "C7")
      (value "10u 25V")
      (footprint "eagle-import:1206-B")
      (libsource (lib "eagle-import") (part "C-EU1206-B"))
    )
    (comp (ref "CF3.2")
      (value "SFM-120-X1-XXX-D")
      (footprint "eagle-import:SFM-120-X1-XXX-D")
      (libsource (lib "eagle-import") (part "SFM-120-X1-XXX-D"))
    )
    (comp (ref "CM3.2")
      (value "J-MOLEX-SMPM-73300-0111X")
      (footprint "eagle-import:J-MOLEX-SMPM-73300-0111X")
      (libsource (lib "eagle-import") (part "J-MOLEX-SMPM-73300-0111X"))
    )
    (comp (ref "C9")
      (value "10u 25V")
      (footprint "eagle-import:1206-B")
      (libsource (lib "eagle-import") (part "C-EU1206-B"))
    )
    (comp (ref "CF5.2")
      (value "SFM-120-X1-XXX-D")
      (footprint "eagle-import:SFM-120-X1-XXX-D")
      (libsource (lib "eagle-import") (part "SFM-120-X1-XXX-D"))
    )
    (comp (ref "J2")
      (value "M55-6001642R")
      (footprint "eagle-import:CONN_M55-6001642R_HRW")
      (fields (field (name "COPYRIGHT") "Copyright (C) 2021 Ultra Librarian. All rights reserved."))
      (libsource (lib "eagle-import") (part "M55-6001642R"))
    )
    (comp (ref "CM8")
      (value "U.FL-R-SMA")
      (footprint "eagle-import:U.FL-R-SMT")
      (libsource (lib "eagle-import") (part "U.FL-R-SMA"))
    )
    (comp (ref "J1")
      (value "5-104196-5")
      (footprint "eagle-import:5-104196-5")
      (libsource (lib "eagle-import") (part "5-104196-5"))
    )
    (comp (ref "C10")
      (value "10u 25V")
      (footprint "eagle-import:1206-B")
      (libsource (lib "eagle-import") (part "C-EU1206-B"))
    )
    (comp (ref "CF6.2")
      (value "SFM-120-X1-XXX-D")
      (footprint "eagle-import:SFM-120-X1-XXX-D")
      (libsource (lib "eagle-import") (part "SFM-120-X1-XXX-D"))
    )
    (comp (ref "C8")
      (value "10u 25V")
      (footprint "eagle-import:1206-B")
      (libsource (lib "eagle-import") (part "C-EU1206-B"))
    )
    (comp (ref "CF4.2")
      (value "SFM-120-X1-XXX-D")
      (footprint "eagle-import:SFM-120-X1-XXX-D")
      (libsource (lib "eagle-import") (part "SFM-120-X1-XXX-D"))
    )
    (comp (ref "CM4.1")
      (value "J-MOLEX-SMPM-73300-0111X")
      (footprint "eagle-import:J-MOLEX-SMPM-73300-0111X")
      (libsource (lib "eagle-import") (part "J-MOLEX-SMPM-73300-0111X"))
    )
    (comp (ref "C1")
      (value "1n")
      (footprint "eagle-import:.0603-C-NOSILK")
      (libsource (lib "eagle-import") (part "C-EU0603-C-NOSILK"))
    )
    (comp (ref "C2")
      (value "1n")
      (footprint "eagle-import:.0603-C-NOSILK")
      (libsource (lib "eagle-import") (part "C-EU0603-C-NOSILK"))
    )
    (comp (ref "C5")
      (value "10u 25V")
      (footprint "eagle-import:1206-B")
      (libsource (lib "eagle-import") (part "C-EU1206-B"))
    )
    (comp (ref "CF1.2")
      (value "SFM-120-X1-XXX-D")
      (footprint "eagle-import:SFM-120-X1-XXX-D")
      (libsource (lib "eagle-import") (part "SFM-120-X1-XXX-D"))
    )
    (comp (ref "CM1.1")
      (value "J-MOLEX-SMPM-73300-0111X")
      (footprint "eagle-import:J-MOLEX-SMPM-73300-0111X")
      (libsource (lib "eagle-import") (part "J-MOLEX-SMPM-73300-0111X"))
    )
    (comp (ref "CM1.2")
      (value "J-MOLEX-SMPM-73300-0111X")
      (footprint "eagle-import:J-MOLEX-SMPM-73300-0111X")
      (libsource (lib "eagle-import") (part "J-MOLEX-SMPM-73300-0111X"))
    )
    (comp (ref "CM1.3")
      (value "J-MOLEX-SMPM-73300-0111X")
      (footprint "eagle-import:J-MOLEX-SMPM-73300-0111X")
      (libsource (lib "eagle-import") (part "J-MOLEX-SMPM-73300-0111X"))
    )
    (comp (ref "FIDUCIAL1")
      (value "FIDUCIAL-1.0X2.0")
      (footprint "eagle-import:FIDUCIAL-1.0X2.0")
      (libsource (lib "eagle-import") (part "FIDUCIAL-1.0X2.0"))
    )
    (comp (ref "FIDUCIAL2")
      (value "FIDUCIAL-1.0X2.0")
      (footprint "eagle-import:FIDUCIAL-1.0X2.0")
      (libsource (lib "eagle-import") (part "FIDUCIAL-1.0X2.0"))
    )
    (comp (ref "FIDUCIAL3")
      (value "FIDUCIAL-1.0X2.0")
      (footprint "eagle-import:FIDUCIAL-1.0X2.0")
      (libsource (lib "eagle-import") (part "FIDUCIAL-1.0X2.0"))
    )
    (comp (ref "R1")
      (value "60.4")
      (footprint "eagle-import:1206-C")
      (libsource (lib "eagle-import") (part "R-US_1206-C"))
    )
    (comp (ref "R2")
      (value "60.4")
      (footprint "eagle-import:1206-C")
      (libsource (lib "eagle-import") (part "R-US_1206-C"))
    )
    (comp (ref "R3")
      (value "60.4")
      (footprint "eagle-import:1206-C")
      (libsource (lib "eagle-import") (part "R-US_1206-C"))
    )
    (comp (ref "R4")
      (value "60.4")
      (footprint "eagle-import:1206-C")
      (libsource (lib "eagle-import") (part "R-US_1206-C"))
    )
    (comp (ref "U$1")
      (value "FLIGHMARKERNEW")
      (footprint "eagle-import:FLIGHTMARKER_NEW_BOARDS")
      (libsource (lib "eagle-import") (part "FLIGHMARKERNEW"))
    )
  )
  (nets
    (net (code "1") (name "C3-UART-RX") (class "Default")
      (node (ref "CF1.2") (pin "38") (pinfunction "38_38") (pintype "passive"))
      (node (ref "CF2.2") (pin "38") (pinfunction "38_38") (pintype "passive"))
      (node (ref "CF3.2") (pin "38") (pinfunction "38_38") (pintype "passive"))
      (node (ref "CF4.2") (pin "38") (pinfunction "38_38") (pintype "passive"))
      (node (ref "CF5.2") (pin "38") (pinfunction "38_38") (pintype "passive"))
      (node (ref "CF6.2") (pin "38") (pinfunction "38_38") (pintype "passive"))
      (node (ref "CF7.2") (pin "38") (pinfunction "38_38") (pintype "passive"))
      (node (ref "J2") (pin "2") (pinfunction "2_2") (pintype "passive"))
    )
    (net (code "2") (name "C3-UART-TX") (class "Default")
      (node (ref "CF1.2") (pin "37") (pinfunction "37_37") (pintype "passive"))
      (node (ref "CF2.2") (pin "37") (pinfunction "37_37") (pintype "passive"))
      (node (ref "CF3.2") (pin "37") (pinfunction "37_37") (pintype "passive"))
      (node (ref "CF4.2") (pin "37") (pinfunction "37_37") (pintype "passive"))
      (node (ref "CF5.2") (pin "37") (pinfunction "37_37") (pintype "passive"))
      (node (ref "CF6.2") (pin "37") (pinfunction "37_37") (pintype "passive"))
      (node (ref "CF7.2") (pin "37") (pinfunction "37_37") (pintype "passive"))
      (node (ref "J2") (pin "3") (pinfunction "3_3") (pintype "passive"))
    )
    (net (code "3") (name "CAN1_H") (class "Default")
      (node (ref "CF1.2") (pin "33") (pinfunction "33_33") (pintype "passive"))
      (node (ref "CF1.2") (pin "34") (pinfunction "34_34") (pintype "passive"))
      (node (ref "CF2.2") (pin "33") (pinfunction "33_33") (pintype "passive"))
      (node (ref "CF2.2") (pin "34") (pinfunction "34_34") (pintype "passive"))
      (node (ref "CF3.2") (pin "33") (pinfunction "33_33") (pintype "passive"))
      (node (ref "CF3.2") (pin "34") (pinfunction "34_34") (pintype "passive"))
      (node (ref "CF4.2") (pin "33") (pinfunction "33_33") (pintype "passive"))
      (node (ref "CF4.2") (pin "34") (pinfunction "34_34") (pintype "passive"))
      (node (ref "CF5.2") (pin "33") (pinfunction "33_33") (pintype "passive"))
      (node (ref "CF5.2") (pin "34") (pinfunction "34_34") (pintype "passive"))
      (node (ref "CF6.2") (pin "33") (pinfunction "33_33") (pintype "passive"))
      (node (ref "CF6.2") (pin "34") (pinfunction "34_34") (pintype "passive"))
      (node (ref "CF7.2") (pin "33") (pinfunction "33_33") (pintype "passive"))
      (node (ref "CF7.2") (pin "34") (pinfunction "34_34") (pintype "passive"))
      (node (ref "J2") (pin "5") (pinfunction "5_5") (pintype "passive"))
      (node (ref "R1") (pin "1") (pinfunction "1_1") (pintype "passive"))
      (node (ref "R10") (pin "1") (pinfunction "1_1") (pintype "passive"))
      (node (ref "R5") (pin "1") (pinfunction "1_1") (pintype "passive"))
    )
    (net (code "4") (name "CAN1_L") (class "Default")
      (node (ref "CF1.2") (pin "35") (pinfunction "35_35") (pintype "passive"))
      (node (ref "CF1.2") (pin "36") (pinfunction "36_36") (pintype "passive"))
      (node (ref "CF2.2") (pin "35") (pinfunction "35_35") (pintype "passive"))
      (node (ref "CF2.2") (pin "36") (pinfunction "36_36") (pintype "passive"))
      (node (ref "CF3.2") (pin "35") (pinfunction "35_35") (pintype "passive"))
      (node (ref "CF3.2") (pin "36") (pinfunction "36_36") (pintype "passive"))
      (node (ref "CF4.2") (pin "35") (pinfunction "35_35") (pintype "passive"))
      (node (ref "CF4.2") (pin "36") (pinfunction "36_36") (pintype "passive"))
      (node (ref "CF5.2") (pin "35") (pinfunction "35_35") (pintype "passive"))
      (node (ref "CF5.2") (pin "36") (pinfunction "36_36") (pintype "passive"))
      (node (ref "CF6.2") (pin "35") (pinfunction "35_35") (pintype "passive"))
      (node (ref "CF6.2") (pin "36") (pinfunction "36_36") (pintype "passive"))
      (node (ref "CF7.2") (pin "35") (pinfunction "35_35") (pintype "passive"))
      (node (ref "CF7.2") (pin "36") (pinfunction "36_36") (pintype "passive"))
      (node (ref "J2") (pin "4") (pinfunction "4_4") (pintype "passive"))
      (node (ref "R2") (pin "1") (pinfunction "1_1") (pintype "passive"))
      (node (ref "R6") (pin "1") (pinfunction "1_1") (pintype "passive"))
      (node (ref "R9") (pin "1") (pinfunction "1_1") (pintype "passive"))
    )
    (net (code "5") (name "CAN2_H") (class "Default")
      (node (ref "CF1.2") (pin "17") (pinfunction "17_17") (pintype "passive"))
      (node (ref "CF1.2") (pin "18") (pinfunction "18_18") (pintype "passive"))
      (node (ref "CF2.2") (pin "17") (pinfunction "17_17") (pintype "passive"))
      (node (ref "CF2.2") (pin "18") (pinfunction "18_18") (pintype "passive"))
      (node (ref "CF3.2") (pin "17") (pinfunction "17_17") (pintype "passive"))
      (node (ref "CF3.2") (pin "18") (pinfunction "18_18") (pintype "passive"))
      (node (ref "CF4.2") (pin "17") (pinfunction "17_17") (pintype "passive"))
      (node (ref "CF4.2") (pin "18") (pinfunction "18_18") (pintype "passive"))
      (node (ref "CF5.2") (pin "17") (pinfunction "17_17") (pintype "passive"))
      (node (ref "CF5.2") (pin "18") (pinfunction "18_18") (pintype "passive"))
      (node (ref "CF6.2") (pin "17") (pinfunction "17_17") (pintype "passive"))
      (node (ref "CF6.2") (pin "18") (pinfunction "18_18") (pintype "passive"))
      (node (ref "CF7.2") (pin "17") (pinfunction "17_17") (pintype "passive"))
      (node (ref "CF7.2") (pin "18") (pinfunction "18_18") (pintype "passive"))
      (node (ref "J2") (pin "13") (pinfunction "13_13") (pintype "passive"))
      (node (ref "R10") (pin "2") (pinfunction "2_2") (pintype "passive"))
      (node (ref "R3") (pin "1") (pinfunction "1_1") (pintype "passive"))
      (node (ref "R7") (pin "1") (pinfunction "1_1") (pintype "passive"))
    )
    (net (code "6") (name "CAN2_L") (class "Default")
      (node (ref "CF1.2") (pin "19") (pinfunction "19_19") (pintype "passive"))
      (node (ref "CF1.2") (pin "20") (pinfunction "20_20") (pintype "passive"))
      (node (ref "CF2.2") (pin "19") (pinfunction "19_19") (pintype "passive"))
      (node (ref "CF2.2") (pin "20") (pinfunction "20_20") (pintype "passive"))
      (node (ref "CF3.2") (pin "19") (pinfunction "19_19") (pintype "passive"))
      (node (ref "CF3.2") (pin "20") (pinfunction "20_20") (pintype "passive"))
      (node (ref "CF4.2") (pin "19") (pinfunction "19_19") (pintype "passive"))
      (node (ref "CF4.2") (pin "20") (pinfunction "20_20") (pintype "passive"))
      (node (ref "CF5.2") (pin "19") (pinfunction "19_19") (pintype "passive"))
      (node (ref "CF5.2") (pin "20") (pinfunction "20_20") (pintype "passive"))
      (node (ref "CF6.2") (pin "19") (pinfunction "19_19") (pintype "passive"))
      (node (ref "CF6.2") (pin "20") (pinfunction "20_20") (pintype "passive"))
      (node (ref "CF7.2") (pin "19") (pinfunction "19_19") (pintype "passive"))
      (node (ref "CF7.2") (pin "20") (pinfunction "20_20") (pintype "passive"))
      (node (ref "J2") (pin "12") (pinfunction "12_12") (pintype "passive"))
      (node (ref "R4") (pin "1") (pinfunction "1_1") (pintype "passive"))
      (node (ref "R8") (pin "1") (pinfunction "1_1") (pintype "passive"))
      (node (ref "R9") (pin "2") (pinfunction "2_2") (pintype "passive"))
    )
    (net (code "7") (name "GND") (class "Default")
      (node (ref "C1") (pin "2") (pinfunction "2_2") (pintype "passive"))
      (node (ref "C10") (pin "2") (pinfunction "2_2") (pintype "passive"))
      (node (ref "C11") (pin "2") (pinfunction "2_2") (pintype "passive"))
      (node (ref "C2") (pin "2") (pinfunction "2_2") (pintype "passive"))
      (node (ref "C3") (pin "2") (pinfunction "2_2") (pintype "passive"))
      (node (ref "C4") (pin "2") (pinfunction "2_2") (pintype "passive"))
      (node (ref "C5") (pin "2") (pinfunction "2_2") (pintype "passive"))
      (node (ref "C6") (pin "2") (pinfunction "2_2") (pintype "passive"))
      (node (ref "C7") (pin "2") (pinfunction "2_2") (pintype "passive"))
      (node (ref "C8") (pin "2") (pinfunction "2_2") (pintype "passive"))
      (node (ref "C9") (pin "2") (pinfunction "2_2") (pintype "passive"))
      (node (ref "CF1.2") (pin "27") (pinfunction "27_27") (pintype "passive"))
      (node (ref "CF1.2") (pin "28") (pinfunction "28_28") (pintype "passive"))
      (node (ref "CF1.2") (pin "29") (pinfunction "29_29") (pintype "passive"))
      (node (ref "CF1.2") (pin "30") (pinfunction "30_30") (pintype "passive"))
      (node (ref "CF1.2") (pin "LC1") (pinfunction "LC1_LC1") (pintype "passive"))
      (node (ref "CF1.2") (pin "LC2") (pinfunction "LC2_LC2") (pintype "passive"))
      (node (ref "CF2.2") (pin "27") (pinfunction "27_27") (pintype "passive"))
      (node (ref "CF2.2") (pin "28") (pinfunction "28_28") (pintype "passive"))
      (node (ref "CF2.2") (pin "29") (pinfunction "29_29") (pintype "passive"))
      (node (ref "CF2.2") (pin "30") (pinfunction "30_30") (pintype "passive"))
      (node (ref "CF2.2") (pin "LC1") (pinfunction "LC1_LC1") (pintype "passive"))
      (node (ref "CF2.2") (pin "LC2") (pinfunction "LC2_LC2") (pintype "passive"))
      (node (ref "CF3.2") (pin "27") (pinfunction "27_27") (pintype "passive"))
      (node (ref "CF3.2") (pin "28") (pinfunction "28_28") (pintype "passive"))
      (node (ref "CF3.2") (pin "29") (pinfunction "29_29") (pintype "passive"))
      (node (ref "CF3.2") (pin "30") (pinfunction "30_30") (pintype "passive"))
      (node (ref "CF3.2") (pin "LC1") (pinfunction "LC1_LC1") (pintype "passive"))
      (node (ref "CF3.2") (pin "LC2") (pinfunction "LC2_LC2") (pintype "passive"))
      (node (ref "CF4.2") (pin "27") (pinfunction "27_27") (pintype "passive"))
      (node (ref "CF4.2") (pin "28") (pinfunction "28_28") (pintype "passive"))
      (node (ref "CF4.2") (pin "29") (pinfunction "29_29") (pintype "passive"))
      (node (ref "CF4.2") (pin "30") (pinfunction "30_30") (pintype "passive"))
      (node (ref "CF4.2") (pin "LC1") (pinfunction "LC1_LC1") (pintype "passive"))
      (node (ref "CF4.2") (pin "LC2") (pinfunction "LC2_LC2") (pintype "passive"))
      (node (ref "CF5.2") (pin "27") (pinfunction "27_27") (pintype "passive"))
      (node (ref "CF5.2") (pin "28") (pinfunction "28_28") (pintype "passive"))
      (node (ref "CF5.2") (pin "29") (pinfunction "29_29") (pintype "passive"))
      (node (ref "CF5.2") (pin "30") (pinfunction "30_30") (pintype "passive"))
      (node (ref "CF5.2") (pin "LC1") (pinfunction "LC1_LC1") (pintype "passive"))
      (node (ref "CF5.2") (pin "LC2") (pinfunction "LC2_LC2") (pintype "passive"))
      (node (ref "CF6.2") (pin "27") (pinfunction "27_27") (pintype "passive"))
      (node (ref "CF6.2") (pin "28") (pinfunction "28_28") (pintype "passive"))
      (node (ref "CF6.2") (pin "29") (pinfunction "29_29") (pintype "passive"))
      (node (ref "CF6.2") (pin "30") (pinfunction "30_30") (pintype "passive"))
      (node (ref "CF6.2") (pin "LC1") (pinfunction "LC1_LC1") (pintype "passive"))
      (node (ref "CF6.2") (pin "LC2") (pinfunction "LC2_LC2") (pintype "passive"))
      (node (ref "CF7.2") (pin "27") (pinfunction "27_27") (pintype "passive"))
      (node (ref "CF7.2") (pin "28") (pinfunction "28_28") (pintype "passive"))
      (node (ref "CF7.2") (pin "29") (pinfunction "29_29") (pintype "passive"))
      (node (ref "CF7.2") (pin "30") (pinfunction "30_30") (pintype "passive"))
      (node (ref "CF7.2") (pin "LC1") (pinfunction "LC1_LC1") (pintype "passive"))
      (node (ref "CF7.2") (pin "LC2") (pinfunction "LC2_LC2") (pintype "passive"))
      (node (ref "CM1.1") (pin "P$1") (pinfunction "SHIELD1_P$1") (pintype "passive"))
      (node (ref "CM1.1") (pin "P$2") (pinfunction "SHIELD1_P$2") (pintype "passive"))
      (node (ref "CM1.1") (pin "P$3") (pinfunction "SHIELD1_P$3") (pintype "passive"))
      (node (ref "CM1.1") (pin "P$4") (pinfunction "SHIELD1_P$4") (pintype "passive"))
      (node (ref "CM1.2") (pin "P$1") (pinfunction "SHIELD1_P$1") (pintype "passive"))
      (node (ref "CM1.2") (pin "P$2") (pinfunction "SHIELD1_P$2") (pintype "passive"))
      (node (ref "CM1.2") (pin "P$3") (pinfunction "SHIELD1_P$3") (pintype "passive"))
      (node (ref "CM1.2") (pin "P$4") (pinfunction "SHIELD1_P$4") (pintype "passive"))
      (node (ref "CM1.3") (pin "P$1") (pinfunction "SHIELD1_P$1") (pintype "passive"))
      (node (ref "CM1.3") (pin "P$2") (pinfunction "SHIELD1_P$2") (pintype "passive"))
      (node (ref "CM1.3") (pin "P$3") (pinfunction "SHIELD1_P$3") (pintype "passive"))
      (node (ref "CM1.3") (pin "P$4") (pinfunction "SHIELD1_P$4") (pintype "passive"))
      (node (ref "CM2.2") (pin "P$1") (pinfunction "SHIELD1_P$1") (pintype "passive"))
      (node (ref "CM2.2") (pin "P$2") (pinfunction "SHIELD1_P$2") (pintype "passive"))
      (node (ref "CM2.2") (pin "P$3") (pinfunction "SHIELD1_P$3") (pintype "passive"))
      (node (ref "CM2.2") (pin "P$4") (pinfunction "SHIELD1_P$4") (pintype "passive"))
      (node (ref "CM2.3") (pin "P$1") (pinfunction "SHIELD1_P$1") (pintype "passive"))
      (node (ref "CM2.3") (pin "P$2") (pinfunction "SHIELD1_P$2") (pintype "passive"))
      (node (ref "CM2.3") (pin "P$3") (pinfunction "SHIELD1_P$3") (pintype "passive"))
      (node (ref "CM2.3") (pin "P$4") (pinfunction "SHIELD1_P$4") (pintype "passive"))
      (node (ref "CM3.2") (pin "P$1") (pinfunction "SHIELD1_P$1") (pintype "passive"))
      (node (ref "CM3.2") (pin "P$2") (pinfunction "SHIELD1_P$2") (pintype "passive"))
      (node (ref "CM3.2") (pin "P$3") (pinfunction "SHIELD1_P$3") (pintype "passive"))
      (node (ref "CM3.2") (pin "P$4") (pinfunction "SHIELD1_P$4") (pintype "passive"))
      (node (ref "CM4.1") (pin "P$1") (pinfunction "SHIELD1_P$1") (pintype "passive"))
      (node (ref "CM4.1") (pin "P$2") (pinfunction "SHIELD1_P$2") (pintype "passive"))
      (node (ref "CM4.1") (pin "P$3") (pinfunction "SHIELD1_P$3") (pintype "passive"))
      (node (ref "CM4.1") (pin "P$4") (pinfunction "SHIELD1_P$4") (pintype "passive"))
      (node (ref "CM8") (pin "2") (pinfunction "P$2_2") (pintype "bidirectional"))
      (node (ref "CM8") (pin "3") (pinfunction "P$2_3") (pintype "bidirectional"))
      (node (ref "J1") (pin "HD1") (pinfunction "HD_HD1") (pintype "passive"))
      (node (ref "J1") (pin "HD2") (pinfunction "HD_HD2") (pintype "passive"))
      (node (ref "J1") (pin "HD3") (pinfunction "HD_HD3") (pintype "passive"))
      (node (ref "J2") (pin "10") (pinfunction "10_10") (pintype "passive"))
      (node (ref "J2") (pin "19") (pinfunction "17_19") (pintype "passive"))
      (node (ref "J2") (pin "20") (pinfunction "17_20") (pintype "passive"))
      (node (ref "J2") (pin "21") (pinfunction "17_21") (pintype "passive"))
      (node (ref "J2") (pin "22") (pinfunction "17_22") (pintype "passive"))
      (node (ref "J2") (pin "6") (pinfunction "6_6") (pintype "passive"))
      (node (ref "J2") (pin "8") (pinfunction "8_8") (pintype "passive"))
    )
    (net (code "8") (name "L-TURNSTILE") (class "Default")
      (node (ref "CM1.2") (pin "RF-DOWN") (pinfunction "RF_RF-DOWN") (pintype "passive"))
      (node (ref "CM2.2") (pin "RF-DOWN") (pinfunction "RF_RF-DOWN") (pintype "passive"))
    )
    (net (code "9") (name "L1-TURNSTILE") (class "Default")
      (node (ref "CM1.1") (pin "RF-DOWN") (pinfunction "RF_RF-DOWN") (pintype "passive"))
      (node (ref "CM3.2") (pin "RF-DOWN") (pinfunction "RF_RF-DOWN") (pintype "passive"))
    )
    (net (code "10") (name "Net-(C1-Pad1)") (class "Default")
      (node (ref "C1") (pin "1") (pinfunction "1_1") (pintype "passive"))
      (node (ref "R1") (pin "2") (pinfunction "2_2") (pintype "passive"))
      (node (ref "R2") (pin "2") (pinfunction "2_2") (pintype "passive"))
    )
    (net (code "11") (name "Net-(C2-Pad1)") (class "Default")
      (node (ref "C2") (pin "1") (pinfunction "1_1") (pintype "passive"))
      (node (ref "R3") (pin "2") (pinfunction "2_2") (pintype "passive"))
      (node (ref "R4") (pin "2") (pinfunction "2_2") (pintype "passive"))
    )
    (net (code "12") (name "Net-(C3-Pad1)") (class "Default")
      (node (ref "C3") (pin "1") (pinfunction "1_1") (pintype "passive"))
      (node (ref "R5") (pin "2") (pinfunction "2_2") (pintype "passive"))
      (node (ref "R6") (pin "2") (pinfunction "2_2") (pintype "passive"))
    )
    (net (code "13") (name "Net-(C4-Pad1)") (class "Default")
      (node (ref "C4") (pin "1") (pinfunction "1_1") (pintype "passive"))
      (node (ref "R7") (pin "2") (pinfunction "2_2") (pintype "passive"))
      (node (ref "R8") (pin "2") (pinfunction "2_2") (pintype "passive"))
    )
    (net (code "14") (name "OPD_PWR") (class "Default")
      (node (ref "CF1.2") (pin "15") (pinfunction "15_15") (pintype "passive"))
      (node (ref "CF1.2") (pin "16") (pinfunction "16_16") (pintype "passive"))
      (node (ref "CF2.2") (pin "15") (pinfunction "15_15") (pintype "passive"))
      (node (ref "CF2.2") (pin "16") (pinfunction "16_16") (pintype "passive"))
      (node (ref "CF3.2") (pin "15") (pinfunction "15_15") (pintype "passive"))
      (node (ref "CF3.2") (pin "16") (pinfunction "16_16") (pintype "passive"))
      (node (ref "CF4.2") (pin "15") (pinfunction "15_15") (pintype "passive"))
      (node (ref "CF4.2") (pin "16") (pinfunction "16_16") (pintype "passive"))
      (node (ref "CF5.2") (pin "15") (pinfunction "15_15") (pintype "passive"))
      (node (ref "CF5.2") (pin "16") (pinfunction "16_16") (pintype "passive"))
      (node (ref "CF6.2") (pin "15") (pinfunction "15_15") (pintype "passive"))
      (node (ref "CF6.2") (pin "16") (pinfunction "16_16") (pintype "passive"))
      (node (ref "CF7.2") (pin "15") (pinfunction "15_15") (pintype "passive"))
      (node (ref "CF7.2") (pin "16") (pinfunction "16_16") (pintype "passive"))
      (node (ref "J2") (pin "14") (pinfunction "14_14") (pintype "passive"))
    )
    (net (code "15") (name "OPD_SCL") (class "Default")
      (node (ref "CF1.2") (pin "13") (pinfunction "13_13") (pintype "passive"))
      (node (ref "CF1.2") (pin "14") (pinfunction "14_14") (pintype "passive"))
      (node (ref "CF2.2") (pin "13") (pinfunction "13_13") (pintype "passive"))
      (node (ref "CF2.2") (pin "14") (pinfunction "14_14") (pintype "passive"))
      (node (ref "CF3.2") (pin "13") (pinfunction "13_13") (pintype "passive"))
      (node (ref "CF3.2") (pin "14") (pinfunction "14_14") (pintype "passive"))
      (node (ref "CF4.2") (pin "13") (pinfunction "13_13") (pintype "passive"))
      (node (ref "CF4.2") (pin "14") (pinfunction "14_14") (pintype "passive"))
      (node (ref "CF5.2") (pin "13") (pinfunction "13_13") (pintype "passive"))
      (node (ref "CF5.2") (pin "14") (pinfunction "14_14") (pintype "passive"))
      (node (ref "CF6.2") (pin "13") (pinfunction "13_13") (pintype "passive"))
      (node (ref "CF6.2") (pin "14") (pinfunction "14_14") (pintype "passive"))
      (node (ref "CF7.2") (pin "13") (pinfunction "13_13") (pintype "passive"))
      (node (ref "CF7.2") (pin "14") (pinfunction "14_14") (pintype "passive"))
      (node (ref "J2") (pin "15") (pinfunction "15_15") (pintype "passive"))
    )
    (net (code "16") (name "OPD_SDA") (class "Default")
      (node (ref "CF1.2") (pin "11") (pinfunction "11_11") (pintype "passive"))
      (node (ref "CF1.2") (pin "12") (pinfunction "12_12") (pintype "passive"))
      (node (ref "CF2.2") (pin "11") (pinfunction "11_11") (pintype "passive"))
      (node (ref "CF2.2") (pin "12") (pinfunction "12_12") (pintype "passive"))
      (node (ref "CF3.2") (pin "11") (pinfunction "11_11") (pintype "passive"))
      (node (ref "CF3.2") (pin "12") (pinfunction "12_12") (pintype "passive"))
      (node (ref "CF4.2") (pin "11") (pinfunction "11_11") (pintype "passive"))
      (node (ref "CF4.2") (pin "12") (pinfunction "12_12") (pintype "passive"))
      (node (ref "CF5.2") (pin "11") (pinfunction "11_11") (pintype "passive"))
      (node (ref "CF5.2") (pin "12") (pinfunction "12_12") (pintype "passive"))
      (node (ref "CF6.2") (pin "11") (pinfunction "11_11") (pintype "passive"))
      (node (ref "CF6.2") (pin "12") (pinfunction "12_12") (pintype "passive"))
      (node (ref "CF7.2") (pin "11") (pinfunction "11_11") (pintype "passive"))
      (node (ref "CF7.2") (pin "12") (pinfunction "12_12") (pintype "passive"))
      (node (ref "J2") (pin "16") (pinfunction "16_16") (pintype "passive"))
    )
    (net (code "17") (name "S-PATCH") (class "Default")
      (node (ref "CM4.1") (pin "RF-DOWN") (pinfunction "RF_RF-DOWN") (pintype "passive"))
      (node (ref "CM8") (pin "1") (pinfunction "P$1_1") (pintype "bidirectional"))
    )
    (net (code "18") (name "SPARE1-MAG-SDA") (class "Default")
      (node (ref "CF1.2") (pin "1") (pinfunction "1_1") (pintype "passive"))
      (node (ref "CF1.2") (pin "2") (pinfunction "2_2") (pintype "passive"))
      (node (ref "CF2.2") (pin "1") (pinfunction "1_1") (pintype "passive"))
      (node (ref "CF2.2") (pin "2") (pinfunction "2_2") (pintype "passive"))
      (node (ref "CF3.2") (pin "1") (pinfunction "1_1") (pintype "passive"))
      (node (ref "CF3.2") (pin "2") (pinfunction "2_2") (pintype "passive"))
      (node (ref "CF4.2") (pin "1") (pinfunction "1_1") (pintype "passive"))
      (node (ref "CF4.2") (pin "2") (pinfunction "2_2") (pintype "passive"))
      (node (ref "CF5.2") (pin "1") (pinfunction "1_1") (pintype "passive"))
      (node (ref "CF5.2") (pin "2") (pinfunction "2_2") (pintype "passive"))
      (node (ref "CF6.2") (pin "1") (pinfunction "1_1") (pintype "passive"))
      (node (ref "CF6.2") (pin "2") (pinfunction "2_2") (pintype "passive"))
      (node (ref "CF7.2") (pin "1") (pinfunction "1_1") (pintype "passive"))
      (node (ref "CF7.2") (pin "2") (pinfunction "2_2") (pintype "passive"))
      (node (ref "J1") (pin "19") (pinfunction "19_19") (pintype "passive"))
      (node (ref "J1") (pin "20") (pinfunction "20_20") (pintype "passive"))
    )
    (net (code "19") (name "SPARE3-MAG-SCL") (class "Default")
      (node (ref "CF1.2") (pin "3") (pinfunction "3_3") (pintype "passive"))
      (node (ref "CF2.2") (pin "3") (pinfunction "3_3") (pintype "passive"))
      (node (ref "CF3.2") (pin "3") (pinfunction "3_3") (pintype "passive"))
      (node (ref "CF4.2") (pin "3") (pinfunction "3_3") (pintype "passive"))
      (node (ref "CF5.2") (pin "3") (pinfunction "3_3") (pintype "passive"))
      (node (ref "CF6.2") (pin "3") (pinfunction "3_3") (pintype "passive"))
      (node (ref "CF7.2") (pin "3") (pinfunction "3_3") (pintype "passive"))
      (node (ref "J1") (pin "18") (pinfunction "18_18") (pintype "passive"))
    )
    (net (code "20") (name "SPARE4-MAG-SCL") (class "Default")
      (node (ref "CF1.2") (pin "4") (pinfunction "4_4") (pintype "passive"))
      (node (ref "CF2.2") (pin "4") (pinfunction "4_4") (pintype "passive"))
      (node (ref "CF3.2") (pin "4") (pinfunction "4_4") (pintype "passive"))
      (node (ref "CF4.2") (pin "4") (pinfunction "4_4") (pintype "passive"))
      (node (ref "CF5.2") (pin "4") (pinfunction "4_4") (pintype "passive"))
      (node (ref "CF6.2") (pin "4") (pinfunction "4_4") (pintype "passive"))
      (node (ref "CF7.2") (pin "4") (pinfunction "4_4") (pintype "passive"))
      (node (ref "J1") (pin "17") (pinfunction "17_17") (pintype "passive"))
    )
    (net (code "21") (name "SPARE5-MAG-POWER") (class "Default")
      (node (ref "CF1.2") (pin "5") (pinfunction "5_5") (pintype "passive"))
      (node (ref "CF2.2") (pin "5") (pinfunction "5_5") (pintype "passive"))
      (node (ref "CF3.2") (pin "5") (pinfunction "5_5") (pintype "passive"))
      (node (ref "CF4.2") (pin "5") (pinfunction "5_5") (pintype "passive"))
      (node (ref "CF5.2") (pin "5") (pinfunction "5_5") (pintype "passive"))
      (node (ref "CF6.2") (pin "5") (pinfunction "5_5") (pintype "passive"))
      (node (ref "CF7.2") (pin "5") (pinfunction "5_5") (pintype "passive"))
      (node (ref "J1") (pin "16") (pinfunction "16_16") (pintype "passive"))
    )
    (net (code "22") (name "SPARE6-MAG-POWER") (class "Default")
      (node (ref "CF1.2") (pin "6") (pinfunction "6_6") (pintype "passive"))
      (node (ref "CF2.2") (pin "6") (pinfunction "6_6") (pintype "passive"))
      (node (ref "CF3.2") (pin "6") (pinfunction "6_6") (pintype "passive"))
      (node (ref "CF4.2") (pin "6") (pinfunction "6_6") (pintype "passive"))
      (node (ref "CF5.2") (pin "6") (pinfunction "6_6") (pintype "passive"))
      (node (ref "CF6.2") (pin "6") (pinfunction "6_6") (pintype "passive"))
      (node (ref "CF7.2") (pin "6") (pinfunction "6_6") (pintype "passive"))
      (node (ref "J1") (pin "15") (pinfunction "15_15") (pintype "passive"))
    )
    (net (code "23") (name "SPARE7") (class "Default")
      (node (ref "CF1.2") (pin "7") (pinfunction "7_7") (pintype "passive"))
      (node (ref "CF2.2") (pin "7") (pinfunction "7_7") (pintype "passive"))
      (node (ref "CF3.2") (pin "7") (pinfunction "7_7") (pintype "passive"))
      (node (ref "CF4.2") (pin "7") (pinfunction "7_7") (pintype "passive"))
      (node (ref "CF5.2") (pin "7") (pinfunction "7_7") (pintype "passive"))
      (node (ref "CF6.2") (pin "7") (pinfunction "7_7") (pintype "passive"))
      (node (ref "CF7.2") (pin "7") (pinfunction "7_7") (pintype "passive"))
      (node (ref "J1") (pin "14") (pinfunction "14_14") (pintype "passive"))
    )
    (net (code "24") (name "SPARE8") (class "Default")
      (node (ref "CF1.2") (pin "8") (pinfunction "8_8") (pintype "passive"))
      (node (ref "CF2.2") (pin "8") (pinfunction "8_8") (pintype "passive"))
      (node (ref "CF3.2") (pin "8") (pinfunction "8_8") (pintype "passive"))
      (node (ref "CF4.2") (pin "8") (pinfunction "8_8") (pintype "passive"))
      (node (ref "CF5.2") (pin "8") (pinfunction "8_8") (pintype "passive"))
      (node (ref "CF6.2") (pin "8") (pinfunction "8_8") (pintype "passive"))
      (node (ref "CF7.2") (pin "8") (pinfunction "8_8") (pintype "passive"))
      (node (ref "J1") (pin "13") (pinfunction "13_13") (pintype "passive"))
    )
    (net (code "25") (name "SPARE9-TURNSTILE-DEPLOY") (class "Default")
      (node (ref "CF1.2") (pin "9") (pinfunction "9_9") (pintype "passive"))
      (node (ref "CF2.2") (pin "9") (pinfunction "9_9") (pintype "passive"))
      (node (ref "CF3.2") (pin "9") (pinfunction "9_9") (pintype "passive"))
      (node (ref "CF4.2") (pin "9") (pinfunction "9_9") (pintype "passive"))
      (node (ref "CF5.2") (pin "9") (pinfunction "9_9") (pintype "passive"))
      (node (ref "CF6.2") (pin "9") (pinfunction "9_9") (pintype "passive"))
      (node (ref "CF7.2") (pin "9") (pinfunction "9_9") (pintype "passive"))
      (node (ref "J1") (pin "12") (pinfunction "12_12") (pintype "passive"))
    )
    (net (code "26") (name "SPARE10-TURNSTILE-DEPLOY") (class "Default")
      (node (ref "CF1.2") (pin "10") (pinfunction "10_10") (pintype "passive"))
      (node (ref "CF2.2") (pin "10") (pinfunction "10_10") (pintype "passive"))
      (node (ref "CF3.2") (pin "10") (pinfunction "10_10") (pintype "passive"))
      (node (ref "CF4.2") (pin "10") (pinfunction "10_10") (pintype "passive"))
      (node (ref "CF5.2") (pin "10") (pinfunction "10_10") (pintype "passive"))
      (node (ref "CF6.2") (pin "10") (pinfunction "10_10") (pintype "passive"))
      (node (ref "CF7.2") (pin "10") (pinfunction "10_10") (pintype "passive"))
      (node (ref "J1") (pin "11") (pinfunction "11_11") (pintype "passive"))
    )
    (net (code "27") (name "SPARE21") (class "Default")
      (node (ref "CF1.2") (pin "21") (pinfunction "21_21") (pintype "passive"))
      (node (ref "CF2.2") (pin "21") (pinfunction "21_21") (pintype "passive"))
      (node (ref "CF3.2") (pin "21") (pinfunction "21_21") (pintype "passive"))
      (node (ref "CF4.2") (pin "21") (pinfunction "21_21") (pintype "passive"))
      (node (ref "CF5.2") (pin "21") (pinfunction "21_21") (pintype "passive"))
      (node (ref "CF6.2") (pin "21") (pinfunction "21_21") (pintype "passive"))
      (node (ref "CF7.2") (pin "21") (pinfunction "21_21") (pintype "passive"))
    )
    (net (code "28") (name "SPARE22") (class "Default")
      (node (ref "CF1.2") (pin "22") (pinfunction "22_22") (pintype "passive"))
      (node (ref "CF2.2") (pin "22") (pinfunction "22_22") (pintype "passive"))
      (node (ref "CF3.2") (pin "22") (pinfunction "22_22") (pintype "passive"))
      (node (ref "CF4.2") (pin "22") (pinfunction "22_22") (pintype "passive"))
      (node (ref "CF5.2") (pin "22") (pinfunction "22_22") (pintype "passive"))
      (node (ref "CF6.2") (pin "22") (pinfunction "22_22") (pintype "passive"))
      (node (ref "CF7.2") (pin "22") (pinfunction "22_22") (pintype "passive"))
    )
    (net (code "29") (name "SPARE31") (class "Default")
      (node (ref "CF1.2") (pin "31") (pinfunction "31_31") (pintype "passive"))
      (node (ref "CF2.2") (pin "31") (pinfunction "31_31") (pintype "passive"))
      (node (ref "CF3.2") (pin "31") (pinfunction "31_31") (pintype "passive"))
      (node (ref "CF4.2") (pin "31") (pinfunction "31_31") (pintype "passive"))
      (node (ref "CF5.2") (pin "31") (pinfunction "31_31") (pintype "passive"))
      (node (ref "CF6.2") (pin "31") (pinfunction "31_31") (pintype "passive"))
      (node (ref "CF7.2") (pin "31") (pinfunction "31_31") (pintype "passive"))
    )
    (net (code "30") (name "SPARE32") (class "Default")
      (node (ref "CF1.2") (pin "32") (pinfunction "32_32") (pintype "passive"))
      (node (ref "CF2.2") (pin "32") (pinfunction "32_32") (pintype "passive"))
      (node (ref "CF3.2") (pin "32") (pinfunction "32_32") (pintype "passive"))
      (node (ref "CF4.2") (pin "32") (pinfunction "32_32") (pintype "passive"))
      (node (ref "CF5.2") (pin "32") (pinfunction "32_32") (pintype "passive"))
      (node (ref "CF6.2") (pin "32") (pinfunction "32_32") (pintype "passive"))
      (node (ref "CF7.2") (pin "32") (pinfunction "32_32") (pintype "passive"))
    )
    (net (code "31") (name "UHF-TURNSTILE") (class "Default")
      (node (ref "CM1.3") (pin "RF-DOWN") (pinfunction "RF_RF-DOWN") (pintype "passive"))
      (node (ref "CM2.3") (pin "RF-DOWN") (pinfunction "RF_RF-DOWN") (pintype "passive"))
    )
    (net (code "32") (name "VBUS") (class "Default")
      (node (ref "C10") (pin "1") (pinfunction "1_1") (pintype "passive"))
      (node (ref "C11") (pin "1") (pinfunction "1_1") (pintype "passive"))
      (node (ref "C5") (pin "1") (pinfunction "1_1") (pintype "passive"))
      (node (ref "C6") (pin "1") (pinfunction "1_1") (pintype "passive"))
      (node (ref "C7") (pin "1") (pinfunction "1_1") (pintype "passive"))
      (node (ref "C8") (pin "1") (pinfunction "1_1") (pintype "passive"))
      (node (ref "C9") (pin "1") (pinfunction "1_1") (pintype "passive"))
      (node (ref "CF1.2") (pin "23") (pinfunction "23_23") (pintype "passive"))
      (node (ref "CF1.2") (pin "24") (pinfunction "24_24") (pintype "passive"))
      (node (ref "CF1.2") (pin "25") (pinfunction "25_25") (pintype "passive"))
      (node (ref "CF1.2") (pin "26") (pinfunction "26_26") (pintype "passive"))
      (node (ref "CF2.2") (pin "23") (pinfunction "23_23") (pintype "passive"))
      (node (ref "CF2.2") (pin "24") (pinfunction "24_24") (pintype "passive"))
      (node (ref "CF2.2") (pin "25") (pinfunction "25_25") (pintype "passive"))
      (node (ref "CF2.2") (pin "26") (pinfunction "26_26") (pintype "passive"))
      (node (ref "CF3.2") (pin "23") (pinfunction "23_23") (pintype "passive"))
      (node (ref "CF3.2") (pin "24") (pinfunction "24_24") (pintype "passive"))
      (node (ref "CF3.2") (pin "25") (pinfunction "25_25") (pintype "passive"))
      (node (ref "CF3.2") (pin "26") (pinfunction "26_26") (pintype "passive"))
      (node (ref "CF4.2") (pin "23") (pinfunction "23_23") (pintype "passive"))
      (node (ref "CF4.2") (pin "24") (pinfunction "24_24") (pintype "passive"))
      (node (ref "CF4.2") (pin "25") (pinfunction "25_25") (pintype "passive"))
      (node (ref "CF4.2") (pin "26") (pinfunction "26_26") (pintype "passive"))
      (node (ref "CF5.2") (pin "23") (pinfunction "23_23") (pintype "passive"))
      (node (ref "CF5.2") (pin "24") (pinfunction "24_24") (pintype "passive"))
      (node (ref "CF5.2") (pin "25") (pinfunction "25_25") (pintype "passive"))
      (node (ref "CF5.2") (pin "26") (pinfunction "26_26") (pintype "passive"))
      (node (ref "CF6.2") (pin "23") (pinfunction "23_23") (pintype "passive"))
      (node (ref "CF6.2") (pin "24") (pinfunction "24_24") (pintype "passive"))
      (node (ref "CF6.2") (pin "25") (pinfunction "25_25") (pintype "passive"))
      (node (ref "CF6.2") (pin "26") (pinfunction "26_26") (pintype "passive"))
      (node (ref "CF7.2") (pin "23") (pinfunction "23_23") (pintype "passive"))
      (node (ref "CF7.2") (pin "24") (pinfunction "24_24") (pintype "passive"))
      (node (ref "CF7.2") (pin "25") (pinfunction "25_25") (pintype "passive"))
      (node (ref "CF7.2") (pin "26") (pinfunction "26_26") (pintype "passive"))
      (node (ref "J2") (pin "11") (pinfunction "11_11") (pintype "passive"))
      (node (ref "J2") (pin "7") (pinfunction "7_7") (pintype "passive"))
      (node (ref "J2") (pin "9") (pinfunction "9_9") (pintype "passive"))
    )
    (net (code "33") (name "unconnected-(FIDUCIAL1-PadFIDUCIAL)") (class "Default")
      (node (ref "FIDUCIAL1") (pin "FIDUCIAL") (pinfunction "FIDUCIAL_FIDUCIAL") (pintype "no_connect"))
    )
    (net (code "34") (name "unconnected-(FIDUCIAL2-PadFIDUCIAL)") (class "Default")
      (node (ref "FIDUCIAL2") (pin "FIDUCIAL") (pinfunction "FIDUCIAL_FIDUCIAL") (pintype "no_connect"))
    )
    (net (code "35") (name "unconnected-(FIDUCIAL3-PadFIDUCIAL)") (class "Default")
      (node (ref "FIDUCIAL3") (pin "FIDUCIAL") (pinfunction "FIDUCIAL_FIDUCIAL") (pintype "no_connect"))
    )
    (net (code "36") (name "unconnected-(J1-Pad1)") (class "Default")
      (node (ref "J1") (pin "1") (pinfunction "1_1") (pintype "passive"))
    )
    (net (code "37") (name "unconnected-(J1-Pad2)") (class "Default")
      (node (ref "J1") (pin "2") (pinfunction "2_2") (pintype "passive"))
    )
    (net (code "38") (name "unconnected-(J1-Pad3)") (class "Default")
      (node (ref "J1") (pin "3") (pinfunction "3_3") (pintype "passive"))
    )
    (net (code "39") (name "unconnected-(J1-Pad4)") (class "Default")
      (node (ref "J1") (pin "4") (pinfunction "4_4") (pintype "passive"))
    )
    (net (code "40") (name "unconnected-(J1-Pad5)") (class "Default")
      (node (ref "J1") (pin "5") (pinfunction "5_5") (pintype "passive"))
    )
    (net (code "41") (name "unconnected-(J1-Pad6)") (class "Default")
      (node (ref "J1") (pin "6") (pinfunction "6_6") (pintype "passive"))
    )
    (net (code "42") (name "unconnected-(J1-Pad7)") (class "Default")
      (node (ref "J1") (pin "7") (pinfunction "7_7") (pintype "passive"))
    )
    (net (code "43") (name "unconnected-(J1-Pad8)") (class "Default")
      (node (ref "J1") (pin "8") (pinfunction "8_8") (pintype "passive"))
    )
    (net (code "44") (name "unconnected-(J1-Pad9)") (class "Default")
      (node (ref "J1") (pin "9") (pinfunction "9_9") (pintype "passive"))
    )
    (net (code "45") (name "unconnected-(J1-Pad10)") (class "Default")
      (node (ref "J1") (pin "10") (pinfunction "10_10") (pintype "passive"))
    )
    (net (code "46") (name "~{SD}") (class "Default")
      (node (ref "CF1.2") (pin "39") (pinfunction "39_39") (pintype "passive"))
      (node (ref "CF1.2") (pin "40") (pinfunction "40_40") (pintype "passive"))
      (node (ref "CF2.2") (pin "39") (pinfunction "39_39") (pintype "passive"))
      (node (ref "CF2.2") (pin "40") (pinfunction "40_40") (pintype "passive"))
      (node (ref "CF3.2") (pin "39") (pinfunction "39_39") (pintype "passive"))
      (node (ref "CF3.2") (pin "40") (pinfunction "40_40") (pintype "passive"))
      (node (ref "CF4.2") (pin "39") (pinfunction "39_39") (pintype "passive"))
      (node (ref "CF4.2") (pin "40") (pinfunction "40_40") (pintype "passive"))
      (node (ref "CF5.2") (pin "39") (pinfunction "39_39") (pintype "passive"))
      (node (ref "CF5.2") (pin "40") (pinfunction "40_40") (pintype "passive"))
      (node (ref "CF6.2") (pin "39") (pinfunction "39_39") (pintype "passive"))
      (node (ref "CF6.2") (pin "40") (pinfunction "40_40") (pintype "passive"))
      (node (ref "CF7.2") (pin "39") (pinfunction "39_39") (pintype "passive"))
      (node (ref "CF7.2") (pin "40") (pinfunction "40_40") (pintype "passive"))
      (node (ref "J2") (pin "1") (pinfunction "1_1") (pintype "passive"))
    )
  )
)
